# 2016_BeaconIR_YahourtPhone.net
KiCad netlist of a schematic drawn in Altium Designer
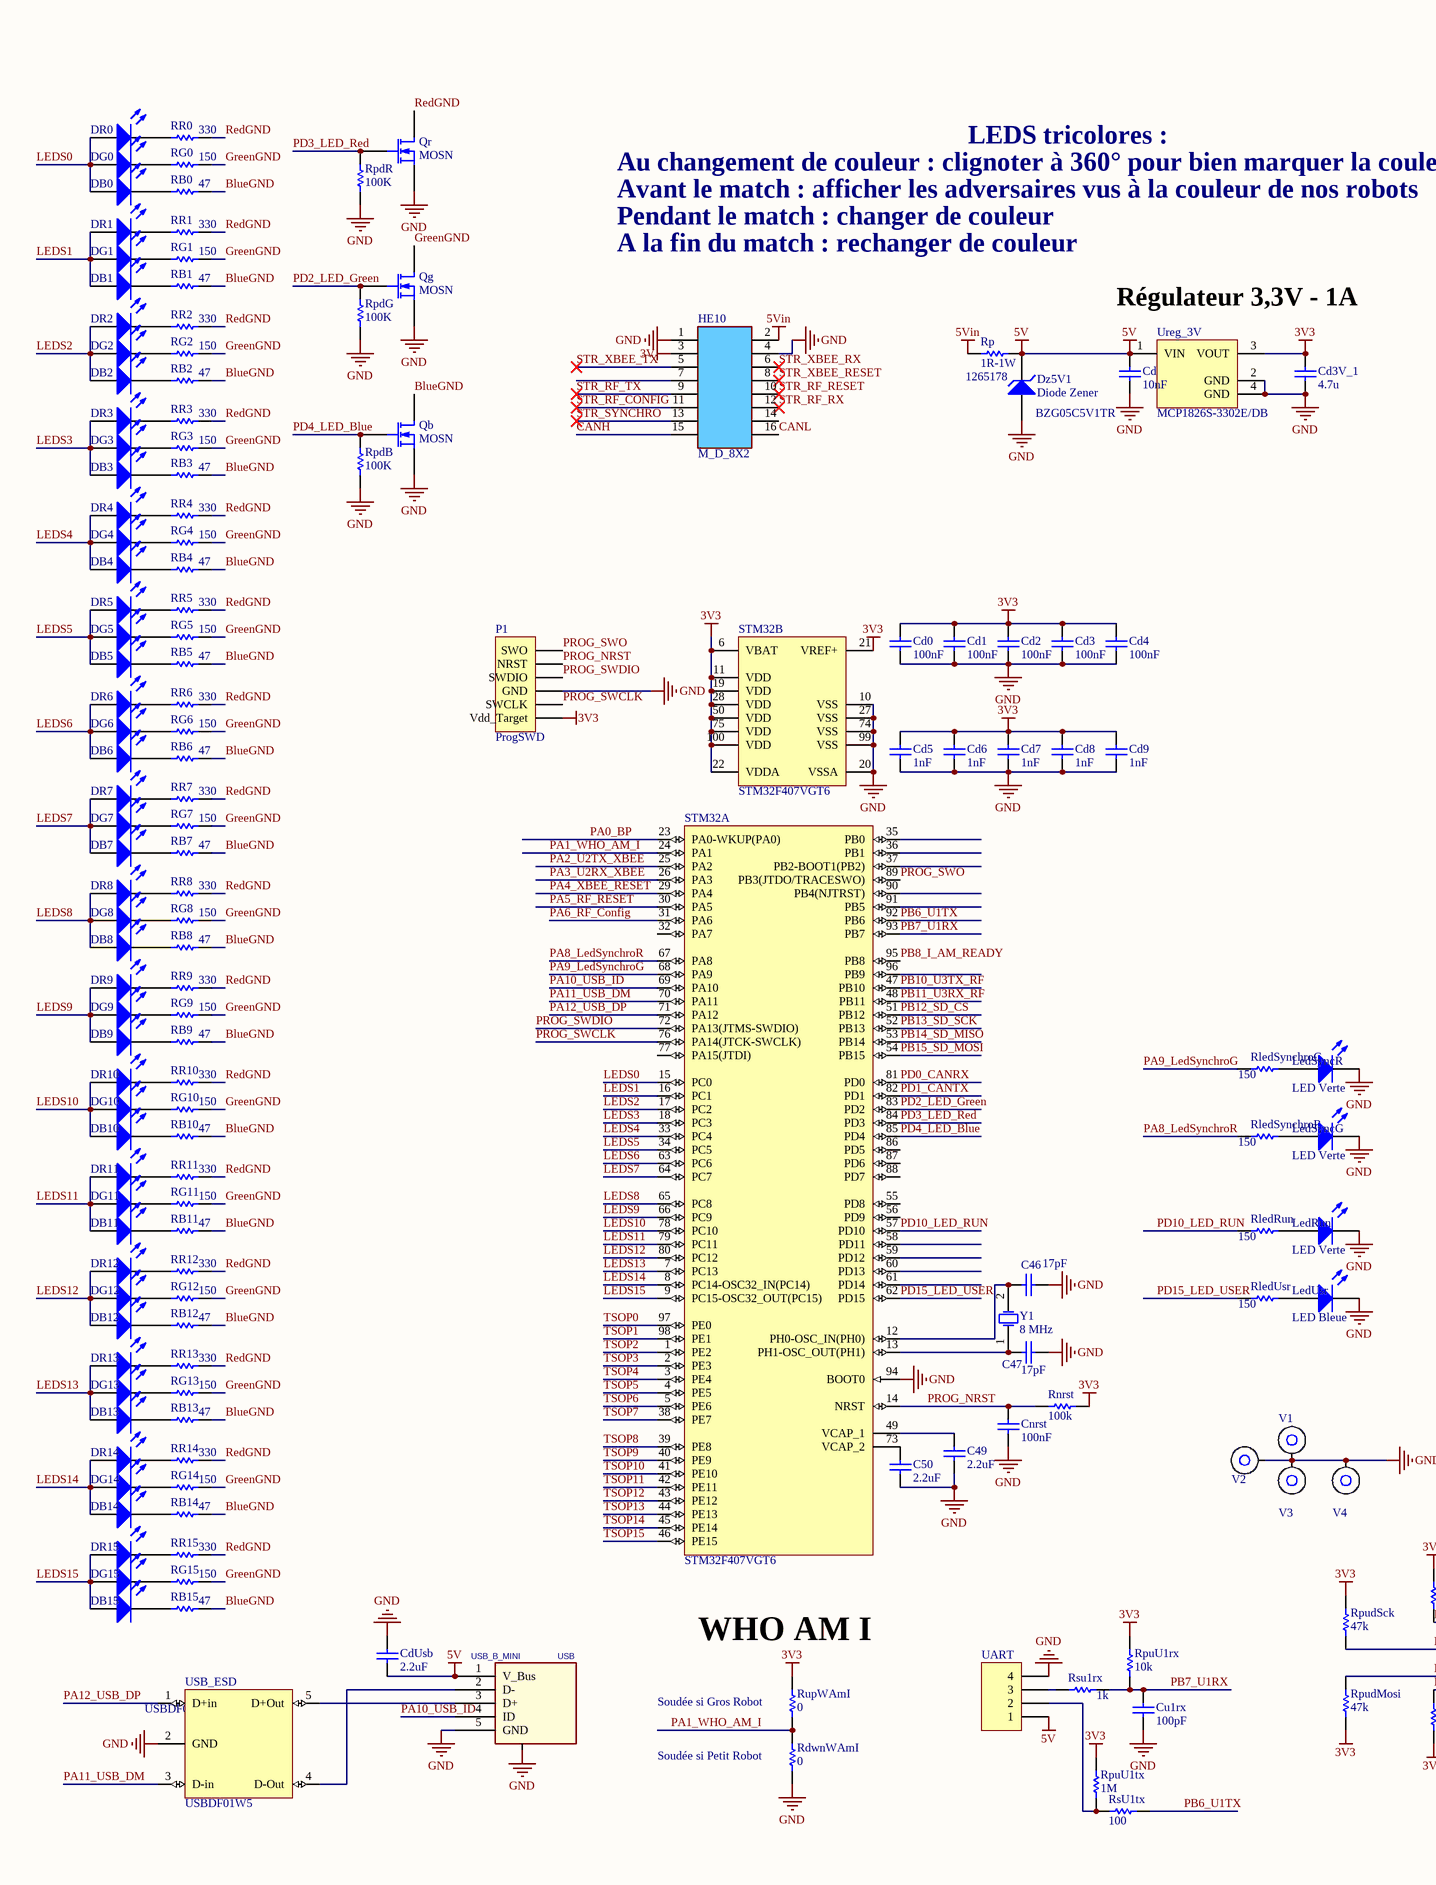
[diagram p0: 2016_BeaconIR_YahourtPhone.SchDoc, left]
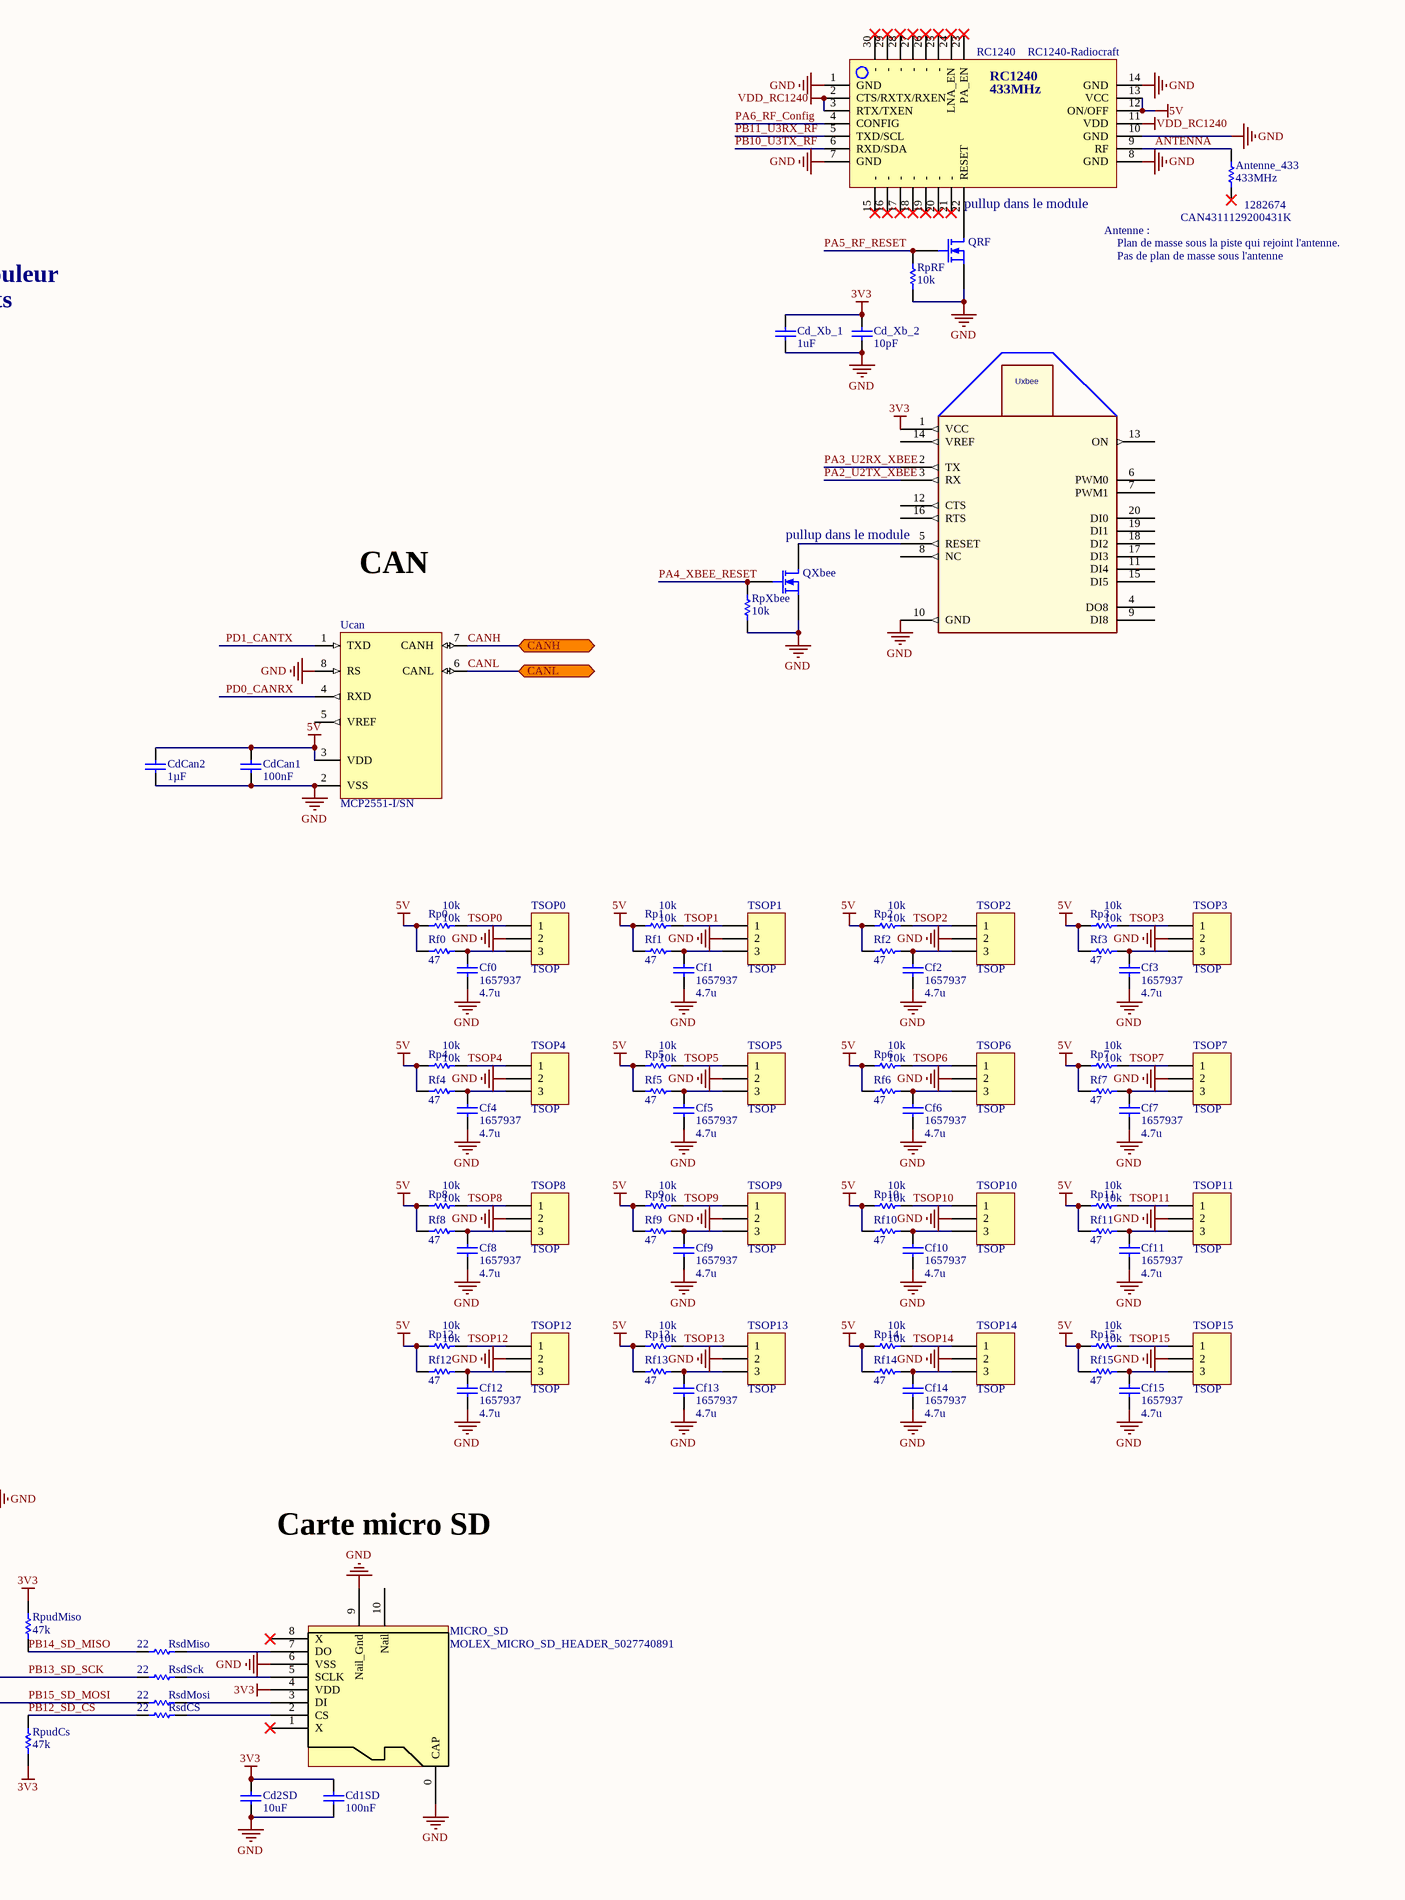
[diagram p1: 2016_BeaconIR_YahourtPhone.SchDoc, middle]
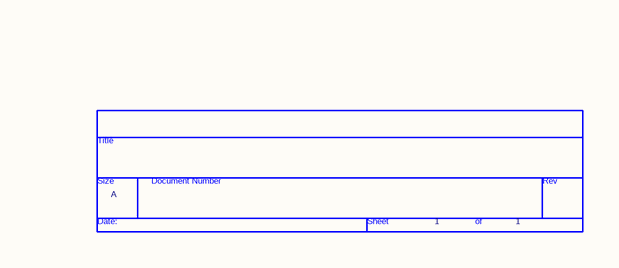
[diagram p2: 2016_BeaconIR_YahourtPhone.SchDoc, right]

(export (version "E")
  (design (tool "Eeschema 10.0.6"))
  (components
    (comp (ref "*")
      (value "TitleBlock0")
      (fields (field (name "PAGE COUNT") "1") (field (name "PAGE NUMBER") "1") (field (name "PAGE SIZE") "A"))
      (libsource (lib "*") (part "TitleBlock0"))
    )
    (comp (ref "Antenne_433")
      (value "433MHz")
      (footprint "R1206_N")
      (description "CAN4311129200431K")
      (fields
        (field (name "PACKAGEREFERENCE") "CAN4311129200431K")
        (field (name "FAR") "1282674")
        (field (name "PUBLISHER") "Altium Limited")
      )
      (libsource (lib "_ROBOT") (part "Resistor"))
    )
    (comp (ref "C46")
      (value "17pF")
      (footprint "C0805_N")
      (description "Capacitor")
      (fields (field (name "PUBLISHER") "Altium Limited"))
      (libsource (lib "_ROBOT") (part "Condensateur"))
    )
    (comp (ref "C47")
      (value "17pF")
      (footprint "C0805_N")
      (description "Capacitor")
      (fields (field (name "PUBLISHER") "Altium Limited"))
      (libsource (lib "_ROBOT") (part "Condensateur"))
    )
    (comp (ref "C49")
      (value "2.2uF")
      (footprint "C0805_N")
      (description "Capacitor")
      (fields (field (name "PUBLISHER") "Altium Limited"))
      (libsource (lib "_ROBOT") (part "Condensateur"))
    )
    (comp (ref "C50")
      (value "2.2uF")
      (footprint "C0805_N")
      (description "Capacitor")
      (fields (field (name "PUBLISHER") "Altium Limited"))
      (libsource (lib "_ROBOT") (part "Condensateur"))
    )
    (comp (ref "Cd")
      (value "10nF")
      (footprint "C1206_N")
      (description "Capacitor")
      (fields (field (name "PUBLISHER") "Altium Limited"))
      (libsource (lib "_ROBOT") (part "Condensateur"))
    )
    (comp (ref "Cd0")
      (value "100nF")
      (footprint "C0805_N")
      (description "Capacitor")
      (fields (field (name "PUBLISHER") "Altium Limited"))
      (libsource (lib "_ROBOT") (part "Condensateur"))
    )
    (comp (ref "Cd1")
      (value "100nF")
      (footprint "C0805_N")
      (description "Capacitor")
      (fields (field (name "PUBLISHER") "Altium Limited"))
      (libsource (lib "_ROBOT") (part "Condensateur"))
    )
    (comp (ref "Cd1SD")
      (value "100nF")
      (footprint "C0805_N")
      (description "Capacitor")
      (fields (field (name "PUBLISHER") "Altium Limited"))
      (libsource (lib "_ROBOT") (part "Condensateur"))
    )
    (comp (ref "Cd2")
      (value "100nF")
      (footprint "C0805_N")
      (description "Capacitor")
      (fields (field (name "PUBLISHER") "Altium Limited"))
      (libsource (lib "_ROBOT") (part "Condensateur"))
    )
    (comp (ref "Cd2SD")
      (value "10uF")
      (footprint "C1206_N")
      (description "Capacitor")
      (fields (field (name "PUBLISHER") "Altium Limited"))
      (libsource (lib "_ROBOT") (part "Condensateur"))
    )
    (comp (ref "Cd3")
      (value "100nF")
      (footprint "C0805_N")
      (description "Capacitor")
      (fields (field (name "PUBLISHER") "Altium Limited"))
      (libsource (lib "_ROBOT") (part "Condensateur"))
    )
    (comp (ref "Cd3V_1")
      (value "4.7u")
      (footprint "C0805_N")
      (description "Capacitor")
      (fields (field (name "PUBLISHER") "Altium Limited"))
      (libsource (lib "DG_Condensateur") (part "Capacitor"))
    )
    (comp (ref "Cd4")
      (value "100nF")
      (footprint "C0805_N")
      (description "Capacitor")
      (fields (field (name "PUBLISHER") "Altium Limited"))
      (libsource (lib "_ROBOT") (part "Condensateur"))
    )
    (comp (ref "Cd5")
      (value "1nF")
      (footprint "C0805_N")
      (description "Capacitor")
      (fields (field (name "PUBLISHER") "Altium Limited"))
      (libsource (lib "_ROBOT") (part "Condensateur"))
    )
    (comp (ref "Cd6")
      (value "1nF")
      (footprint "C0805_N")
      (description "Capacitor")
      (fields (field (name "PUBLISHER") "Altium Limited"))
      (libsource (lib "_ROBOT") (part "Condensateur"))
    )
    (comp (ref "Cd7")
      (value "1nF")
      (footprint "C0805_N")
      (description "Capacitor")
      (fields (field (name "PUBLISHER") "Altium Limited"))
      (libsource (lib "_ROBOT") (part "Condensateur"))
    )
    (comp (ref "Cd8")
      (value "1nF")
      (footprint "C0805_N")
      (description "Capacitor")
      (fields (field (name "PUBLISHER") "Altium Limited"))
      (libsource (lib "_ROBOT") (part "Condensateur"))
    )
    (comp (ref "Cd9")
      (value "1nF")
      (footprint "C0805_N")
      (description "Capacitor")
      (fields (field (name "PUBLISHER") "Altium Limited"))
      (libsource (lib "_ROBOT") (part "Condensateur"))
    )
    (comp (ref "CdCan1")
      (value "100nF")
      (footprint "C0805_N")
      (description "Capacitor")
      (fields (field (name "PUBLISHER") "Altium Limited"))
      (libsource (lib "_ROBOT") (part "Condensateur"))
    )
    (comp (ref "CdCan2")
      (value "1µF")
      (footprint "C0805_N")
      (description "Capacitor")
      (fields (field (name "PUBLISHER") "Altium Limited"))
      (libsource (lib "_ROBOT") (part "Condensateur"))
    )
    (comp (ref "CdUsb")
      (value "2.2uF")
      (footprint "C0805_N")
      (description "Capacitor")
      (fields (field (name "PUBLISHER") "Altium Limited"))
      (libsource (lib "_ROBOT") (part "Condensateur"))
    )
    (comp (ref "Cd_Xb_1")
      (value "1uF")
      (footprint "C0805_N")
      (description "Capacitor")
      (fields (field (name "PUBLISHER") "Altium Limited"))
      (libsource (lib "_ROBOT") (part "Condensateur"))
    )
    (comp (ref "Cd_Xb_2")
      (value "10pF")
      (footprint "C0805_N")
      (description "Capacitor")
      (fields (field (name "PUBLISHER") "Altium Limited"))
      (libsource (lib "_ROBOT") (part "Condensateur"))
    )
    (comp (ref "Cf0")
      (value "1657937")
      (footprint "C1206_N")
      (description "Capacitor")
      (fields (field (name "ALTIUM_VALUE") "4.7u") (field (name "PUBLISHER") "Altium Limited"))
      (libsource (lib "Robot2010") (part "CONDENSATEUR"))
    )
    (comp (ref "Cf1")
      (value "1657937")
      (footprint "C1206_N")
      (description "Capacitor")
      (fields (field (name "ALTIUM_VALUE") "4.7u") (field (name "PUBLISHER") "Altium Limited"))
      (libsource (lib "Robot2010") (part "CONDENSATEUR"))
    )
    (comp (ref "Cf2")
      (value "1657937")
      (footprint "C1206_N")
      (description "Capacitor")
      (fields (field (name "ALTIUM_VALUE") "4.7u") (field (name "PUBLISHER") "Altium Limited"))
      (libsource (lib "Robot2010") (part "CONDENSATEUR"))
    )
    (comp (ref "Cf3")
      (value "1657937")
      (footprint "C1206_N")
      (description "Capacitor")
      (fields (field (name "ALTIUM_VALUE") "4.7u") (field (name "PUBLISHER") "Altium Limited"))
      (libsource (lib "Robot2010") (part "CONDENSATEUR"))
    )
    (comp (ref "Cf4")
      (value "1657937")
      (footprint "C1206_N")
      (description "Capacitor")
      (fields (field (name "ALTIUM_VALUE") "4.7u") (field (name "PUBLISHER") "Altium Limited"))
      (libsource (lib "Robot2010") (part "CONDENSATEUR"))
    )
    (comp (ref "Cf5")
      (value "1657937")
      (footprint "C1206_N")
      (description "Capacitor")
      (fields (field (name "ALTIUM_VALUE") "4.7u") (field (name "PUBLISHER") "Altium Limited"))
      (libsource (lib "Robot2010") (part "CONDENSATEUR"))
    )
    (comp (ref "Cf6")
      (value "1657937")
      (footprint "C1206_N")
      (description "Capacitor")
      (fields (field (name "ALTIUM_VALUE") "4.7u") (field (name "PUBLISHER") "Altium Limited"))
      (libsource (lib "Robot2010") (part "CONDENSATEUR"))
    )
    (comp (ref "Cf7")
      (value "1657937")
      (footprint "C1206_N")
      (description "Capacitor")
      (fields (field (name "ALTIUM_VALUE") "4.7u") (field (name "PUBLISHER") "Altium Limited"))
      (libsource (lib "Robot2010") (part "CONDENSATEUR"))
    )
    (comp (ref "Cf8")
      (value "1657937")
      (footprint "C1206_N")
      (description "Capacitor")
      (fields (field (name "ALTIUM_VALUE") "4.7u") (field (name "PUBLISHER") "Altium Limited"))
      (libsource (lib "Robot2010") (part "CONDENSATEUR"))
    )
    (comp (ref "Cf9")
      (value "1657937")
      (footprint "C1206_N")
      (description "Capacitor")
      (fields (field (name "ALTIUM_VALUE") "4.7u") (field (name "PUBLISHER") "Altium Limited"))
      (libsource (lib "Robot2010") (part "CONDENSATEUR"))
    )
    (comp (ref "Cf10")
      (value "1657937")
      (footprint "C1206_N")
      (description "Capacitor")
      (fields (field (name "ALTIUM_VALUE") "4.7u") (field (name "PUBLISHER") "Altium Limited"))
      (libsource (lib "Robot2010") (part "CONDENSATEUR"))
    )
    (comp (ref "Cf11")
      (value "1657937")
      (footprint "C1206_N")
      (description "Capacitor")
      (fields (field (name "ALTIUM_VALUE") "4.7u") (field (name "PUBLISHER") "Altium Limited"))
      (libsource (lib "Robot2010") (part "CONDENSATEUR"))
    )
    (comp (ref "Cf12")
      (value "1657937")
      (footprint "C1206_N")
      (description "Capacitor")
      (fields (field (name "ALTIUM_VALUE") "4.7u") (field (name "PUBLISHER") "Altium Limited"))
      (libsource (lib "Robot2010") (part "CONDENSATEUR"))
    )
    (comp (ref "Cf13")
      (value "1657937")
      (footprint "C1206_N")
      (description "Capacitor")
      (fields (field (name "ALTIUM_VALUE") "4.7u") (field (name "PUBLISHER") "Altium Limited"))
      (libsource (lib "Robot2010") (part "CONDENSATEUR"))
    )
    (comp (ref "Cf14")
      (value "1657937")
      (footprint "C1206_N")
      (description "Capacitor")
      (fields (field (name "ALTIUM_VALUE") "4.7u") (field (name "PUBLISHER") "Altium Limited"))
      (libsource (lib "Robot2010") (part "CONDENSATEUR"))
    )
    (comp (ref "Cf15")
      (value "1657937")
      (footprint "C1206_N")
      (description "Capacitor")
      (fields (field (name "ALTIUM_VALUE") "4.7u") (field (name "PUBLISHER") "Altium Limited"))
      (libsource (lib "Robot2010") (part "CONDENSATEUR"))
    )
    (comp (ref "Cnrst")
      (value "100nF")
      (footprint "C0805_N")
      (description "Capacitor")
      (fields (field (name "PUBLISHER") "Altium Limited"))
      (libsource (lib "_ROBOT") (part "Condensateur"))
    )
    (comp (ref "Cu1rx")
      (value "100pF")
      (footprint "C0805_N")
      (description "Capacitor")
      (fields (field (name "PUBLISHER") "Altium Limited"))
      (libsource (lib "_ROBOT") (part "Condensateur"))
    )
    (comp (ref "DB0")
      (value "LED")
      (footprint "LED_sideView_1204")
      (description "Typical LED")
      (fields (field (name "PUBLISHER") "Altium Limited"))
      (libsource (lib "DG_LED") (part "LED"))
    )
    (comp (ref "DB1")
      (value "LED")
      (footprint "LED_sideView_1204")
      (description "Typical LED")
      (fields (field (name "PUBLISHER") "Altium Limited"))
      (libsource (lib "DG_LED") (part "LED"))
    )
    (comp (ref "DB2")
      (value "LED")
      (footprint "LED_sideView_1204")
      (description "Typical LED")
      (fields (field (name "PUBLISHER") "Altium Limited"))
      (libsource (lib "DG_LED") (part "LED"))
    )
    (comp (ref "DB3")
      (value "LED")
      (footprint "LED_sideView_1204")
      (description "Typical LED")
      (fields (field (name "PUBLISHER") "Altium Limited"))
      (libsource (lib "DG_LED") (part "LED"))
    )
    (comp (ref "DB4")
      (value "LED")
      (footprint "LED_sideView_1204")
      (description "Typical LED")
      (fields (field (name "PUBLISHER") "Altium Limited"))
      (libsource (lib "DG_LED") (part "LED"))
    )
    (comp (ref "DB5")
      (value "LED")
      (footprint "LED_sideView_1204")
      (description "Typical LED")
      (fields (field (name "PUBLISHER") "Altium Limited"))
      (libsource (lib "DG_LED") (part "LED"))
    )
    (comp (ref "DB6")
      (value "LED")
      (footprint "LED_sideView_1204")
      (description "Typical LED")
      (fields (field (name "PUBLISHER") "Altium Limited"))
      (libsource (lib "DG_LED") (part "LED"))
    )
    (comp (ref "DB7")
      (value "LED")
      (footprint "LED_sideView_1204")
      (description "Typical LED")
      (fields (field (name "PUBLISHER") "Altium Limited"))
      (libsource (lib "DG_LED") (part "LED"))
    )
    (comp (ref "DB8")
      (value "LED")
      (footprint "LED_sideView_1204")
      (description "Typical LED")
      (fields (field (name "PUBLISHER") "Altium Limited"))
      (libsource (lib "DG_LED") (part "LED"))
    )
    (comp (ref "DB9")
      (value "LED")
      (footprint "LED_sideView_1204")
      (description "Typical LED")
      (fields (field (name "PUBLISHER") "Altium Limited"))
      (libsource (lib "DG_LED") (part "LED"))
    )
    (comp (ref "DB10")
      (value "LED")
      (footprint "LED_sideView_1204")
      (description "Typical LED")
      (fields (field (name "PUBLISHER") "Altium Limited"))
      (libsource (lib "DG_LED") (part "LED"))
    )
    (comp (ref "DB11")
      (value "LED")
      (footprint "LED_sideView_1204")
      (description "Typical LED")
      (fields (field (name "PUBLISHER") "Altium Limited"))
      (libsource (lib "DG_LED") (part "LED"))
    )
    (comp (ref "DB12")
      (value "LED")
      (footprint "LED_sideView_1204")
      (description "Typical LED")
      (fields (field (name "PUBLISHER") "Altium Limited"))
      (libsource (lib "DG_LED") (part "LED"))
    )
    (comp (ref "DB13")
      (value "LED")
      (footprint "LED_sideView_1204")
      (description "Typical LED")
      (fields (field (name "PUBLISHER") "Altium Limited"))
      (libsource (lib "DG_LED") (part "LED"))
    )
    (comp (ref "DB14")
      (value "LED")
      (footprint "LED_sideView_1204")
      (description "Typical LED")
      (fields (field (name "PUBLISHER") "Altium Limited"))
      (libsource (lib "DG_LED") (part "LED"))
    )
    (comp (ref "DB15")
      (value "LED")
      (footprint "LED_sideView_1204")
      (description "Typical LED")
      (fields (field (name "PUBLISHER") "Altium Limited"))
      (libsource (lib "DG_LED") (part "LED"))
    )
    (comp (ref "DG0")
      (value "LED")
      (footprint "LED_sideView_1204")
      (description "Typical LED")
      (fields (field (name "PUBLISHER") "Altium Limited"))
      (libsource (lib "DG_LED") (part "LED"))
    )
    (comp (ref "DG1")
      (value "LED")
      (footprint "LED_sideView_1204")
      (description "Typical LED")
      (fields (field (name "PUBLISHER") "Altium Limited"))
      (libsource (lib "DG_LED") (part "LED"))
    )
    (comp (ref "DG2")
      (value "LED")
      (footprint "LED_sideView_1204")
      (description "Typical LED")
      (fields (field (name "PUBLISHER") "Altium Limited"))
      (libsource (lib "DG_LED") (part "LED"))
    )
    (comp (ref "DG3")
      (value "LED")
      (footprint "LED_sideView_1204")
      (description "Typical LED")
      (fields (field (name "PUBLISHER") "Altium Limited"))
      (libsource (lib "DG_LED") (part "LED"))
    )
    (comp (ref "DG4")
      (value "LED")
      (footprint "LED_sideView_1204")
      (description "Typical LED")
      (fields (field (name "PUBLISHER") "Altium Limited"))
      (libsource (lib "DG_LED") (part "LED"))
    )
    (comp (ref "DG5")
      (value "LED")
      (footprint "LED_sideView_1204")
      (description "Typical LED")
      (fields (field (name "PUBLISHER") "Altium Limited"))
      (libsource (lib "DG_LED") (part "LED"))
    )
    (comp (ref "DG6")
      (value "LED")
      (footprint "LED_sideView_1204")
      (description "Typical LED")
      (fields (field (name "PUBLISHER") "Altium Limited"))
      (libsource (lib "DG_LED") (part "LED"))
    )
    (comp (ref "DG7")
      (value "LED")
      (footprint "LED_sideView_1204")
      (description "Typical LED")
      (fields (field (name "PUBLISHER") "Altium Limited"))
      (libsource (lib "DG_LED") (part "LED"))
    )
    (comp (ref "DG8")
      (value "LED")
      (footprint "LED_sideView_1204")
      (description "Typical LED")
      (fields (field (name "PUBLISHER") "Altium Limited"))
      (libsource (lib "DG_LED") (part "LED"))
    )
    (comp (ref "DG9")
      (value "LED")
      (footprint "LED_sideView_1204")
      (description "Typical LED")
      (fields (field (name "PUBLISHER") "Altium Limited"))
      (libsource (lib "DG_LED") (part "LED"))
    )
    (comp (ref "DG10")
      (value "LED")
      (footprint "LED_sideView_1204")
      (description "Typical LED")
      (fields (field (name "PUBLISHER") "Altium Limited"))
      (libsource (lib "DG_LED") (part "LED"))
    )
    (comp (ref "DG11")
      (value "LED")
      (footprint "LED_sideView_1204")
      (description "Typical LED")
      (fields (field (name "PUBLISHER") "Altium Limited"))
      (libsource (lib "DG_LED") (part "LED"))
    )
    (comp (ref "DG12")
      (value "LED")
      (footprint "LED_sideView_1204")
      (description "Typical LED")
      (fields (field (name "PUBLISHER") "Altium Limited"))
      (libsource (lib "DG_LED") (part "LED"))
    )
    (comp (ref "DG13")
      (value "LED")
      (footprint "LED_sideView_1204")
      (description "Typical LED")
      (fields (field (name "PUBLISHER") "Altium Limited"))
      (libsource (lib "DG_LED") (part "LED"))
    )
    (comp (ref "DG14")
      (value "LED")
      (footprint "LED_sideView_1204")
      (description "Typical LED")
      (fields (field (name "PUBLISHER") "Altium Limited"))
      (libsource (lib "DG_LED") (part "LED"))
    )
    (comp (ref "DG15")
      (value "LED")
      (footprint "LED_sideView_1204")
      (description "Typical LED")
      (fields (field (name "PUBLISHER") "Altium Limited"))
      (libsource (lib "DG_LED") (part "LED"))
    )
    (comp (ref "DR0")
      (value "LED")
      (footprint "LED_sideView_1204")
      (description "Typical LED")
      (fields (field (name "PUBLISHER") "Altium Limited"))
      (libsource (lib "DG_LED") (part "LED"))
    )
    (comp (ref "DR1")
      (value "LED")
      (footprint "LED_sideView_1204")
      (description "Typical LED")
      (fields (field (name "PUBLISHER") "Altium Limited"))
      (libsource (lib "DG_LED") (part "LED"))
    )
    (comp (ref "DR2")
      (value "LED")
      (footprint "LED_sideView_1204")
      (description "Typical LED")
      (fields (field (name "PUBLISHER") "Altium Limited"))
      (libsource (lib "DG_LED") (part "LED"))
    )
    (comp (ref "DR3")
      (value "LED")
      (footprint "LED_sideView_1204")
      (description "Typical LED")
      (fields (field (name "PUBLISHER") "Altium Limited"))
      (libsource (lib "DG_LED") (part "LED"))
    )
    (comp (ref "DR4")
      (value "LED")
      (footprint "LED_sideView_1204")
      (description "Typical LED")
      (fields (field (name "PUBLISHER") "Altium Limited"))
      (libsource (lib "DG_LED") (part "LED"))
    )
    (comp (ref "DR5")
      (value "LED")
      (footprint "LED_sideView_1204")
      (description "Typical LED")
      (fields (field (name "PUBLISHER") "Altium Limited"))
      (libsource (lib "DG_LED") (part "LED"))
    )
    (comp (ref "DR6")
      (value "LED")
      (footprint "LED_sideView_1204")
      (description "Typical LED")
      (fields (field (name "PUBLISHER") "Altium Limited"))
      (libsource (lib "DG_LED") (part "LED"))
    )
    (comp (ref "DR7")
      (value "LED")
      (footprint "LED_sideView_1204")
      (description "Typical LED")
      (fields (field (name "PUBLISHER") "Altium Limited"))
      (libsource (lib "DG_LED") (part "LED"))
    )
    (comp (ref "DR8")
      (value "LED")
      (footprint "LED_sideView_1204")
      (description "Typical LED")
      (fields (field (name "PUBLISHER") "Altium Limited"))
      (libsource (lib "DG_LED") (part "LED"))
    )
    (comp (ref "DR9")
      (value "LED")
      (footprint "LED_sideView_1204")
      (description "Typical LED")
      (fields (field (name "PUBLISHER") "Altium Limited"))
      (libsource (lib "DG_LED") (part "LED"))
    )
    (comp (ref "DR10")
      (value "LED")
      (footprint "LED_sideView_1204")
      (description "Typical LED")
      (fields (field (name "PUBLISHER") "Altium Limited"))
      (libsource (lib "DG_LED") (part "LED"))
    )
    (comp (ref "DR11")
      (value "LED")
      (footprint "LED_sideView_1204")
      (description "Typical LED")
      (fields (field (name "PUBLISHER") "Altium Limited"))
      (libsource (lib "DG_LED") (part "LED"))
    )
    (comp (ref "DR12")
      (value "LED")
      (footprint "LED_sideView_1204")
      (description "Typical LED")
      (fields (field (name "PUBLISHER") "Altium Limited"))
      (libsource (lib "DG_LED") (part "LED"))
    )
    (comp (ref "DR13")
      (value "LED")
      (footprint "LED_sideView_1204")
      (description "Typical LED")
      (fields (field (name "PUBLISHER") "Altium Limited"))
      (libsource (lib "DG_LED") (part "LED"))
    )
    (comp (ref "DR14")
      (value "LED")
      (footprint "LED_sideView_1204")
      (description "Typical LED")
      (fields (field (name "PUBLISHER") "Altium Limited"))
      (libsource (lib "DG_LED") (part "LED"))
    )
    (comp (ref "DR15")
      (value "LED")
      (footprint "LED_sideView_1204")
      (description "Typical LED")
      (fields (field (name "PUBLISHER") "Altium Limited"))
      (libsource (lib "DG_LED") (part "LED"))
    )
    (comp (ref "Dz5V1")
      (value "Diode Zener")
      (footprint "SMA Diode")
      (description "Zener Diode")
      (fields (field (name "ALTIUM_UNNAMED_1") "BZG05C5V1TR"))
      (libsource (lib "_ROBOT") (part "Diode Zener"))
    )
    (comp (ref "HE10")
      (value "BARRETTE_8 CONTACTS_2 RANGEES_MALE_DROITE")
      (footprint "HE10/16_M_D_B P")
      (fields (field (name "TYPE") "M_D_8X2"))
      (libsource (lib "connecteurs") (part "BARRETTE_8 CONTACTS_2 RANGEES_MALE_DROITE"))
    )
    (comp (ref "LedRun")
      (value "LED Verte")
      (footprint "LED_0805")
      (description "Typical LED")
      (fields (field (name "PUBLISHER") "Altium Limited"))
      (libsource (lib "DG_LED") (part "LED"))
    )
    (comp (ref "LedSyncG")
      (value "LED Verte")
      (footprint "LED_0805")
      (description "Typical LED")
      (fields (field (name "PUBLISHER") "Altium Limited"))
      (libsource (lib "DG_LED") (part "LED"))
    )
    (comp (ref "LedSyncR")
      (value "LED Verte")
      (footprint "LED_0805")
      (description "Typical LED")
      (fields (field (name "PUBLISHER") "Altium Limited"))
      (libsource (lib "DG_LED") (part "LED"))
    )
    (comp (ref "LedUsr")
      (value "LED Bleue")
      (footprint "LED_0805")
      (description "Typical LED")
      (fields (field (name "PUBLISHER") "Altium Limited"))
      (libsource (lib "DG_LED") (part "LED"))
    )
    (comp (ref "MICRO_SD")
      (value "MOLEX_MICRO_SD_HEADER_5027740891")
      (footprint "MOLEX_MICRO_SD_HEADER_5027740891")
      (libsource (lib "Connecteur") (part "MOLEX_MICRO_SD_HEADER_5027740891"))
    )
    (comp (ref "P1")
      (value "ProgSWD")
      (footprint "HDR1X6")
      (description "Header, 6-Pin")
      (fields (field (name "PUBLISHER") "Altium Limited"))
      (libsource (lib "DG_Connecteur") (part "Header 6"))
    )
    (comp (ref "Qb")
      (value "MOSN")
      (footprint "SOT23-3N")
      (description "N-Channel MOSFET")
      (fields (field (name "PUBLISHER") "Altium Limited"))
      (libsource (lib "_ROBOT") (part "Transistor MOSFET-N"))
    )
    (comp (ref "Qg")
      (value "MOSN")
      (footprint "SOT23-3N")
      (description "N-Channel MOSFET")
      (fields (field (name "PUBLISHER") "Altium Limited"))
      (libsource (lib "_ROBOT") (part "Transistor MOSFET-N"))
    )
    (comp (ref "Qr")
      (value "MOSN")
      (footprint "SOT23-3N")
      (description "N-Channel MOSFET")
      (fields (field (name "PUBLISHER") "Altium Limited"))
      (libsource (lib "_ROBOT") (part "Transistor MOSFET-N"))
    )
    (comp (ref "QRF")
      (value "Transistor MOSFET-N")
      (footprint "SOT23-3N")
      (description "N-Channel MOSFET")
      (fields (field (name "PUBLISHER") "Altium Limited"))
      (libsource (lib "_ROBOT") (part "Transistor MOSFET-N"))
    )
    (comp (ref "QXbee")
      (value "Transistor MOSFET-N")
      (footprint "SOT23-3N")
      (description "N-Channel MOSFET")
      (fields (field (name "PUBLISHER") "Altium Limited"))
      (libsource (lib "_ROBOT") (part "Transistor MOSFET-N"))
    )
    (comp (ref "RB0")
      (value "47")
      (footprint "R1206_N")
      (description "Resistor")
      (fields (field (name "PUBLISHER") "Altium Limited"))
      (libsource (lib "_ROBOT") (part "Resistor"))
    )
    (comp (ref "RB1")
      (value "47")
      (footprint "R1206_N")
      (description "Resistor")
      (fields (field (name "PUBLISHER") "Altium Limited"))
      (libsource (lib "_ROBOT") (part "Resistor"))
    )
    (comp (ref "RB2")
      (value "47")
      (footprint "R1206_N")
      (description "Resistor")
      (fields (field (name "PUBLISHER") "Altium Limited"))
      (libsource (lib "_ROBOT") (part "Resistor"))
    )
    (comp (ref "RB3")
      (value "47")
      (footprint "R1206_N")
      (description "Resistor")
      (fields (field (name "PUBLISHER") "Altium Limited"))
      (libsource (lib "_ROBOT") (part "Resistor"))
    )
    (comp (ref "RB4")
      (value "47")
      (footprint "R1206_N")
      (description "Resistor")
      (fields (field (name "PUBLISHER") "Altium Limited"))
      (libsource (lib "_ROBOT") (part "Resistor"))
    )
    (comp (ref "RB5")
      (value "47")
      (footprint "R1206_N")
      (description "Resistor")
      (fields (field (name "PUBLISHER") "Altium Limited"))
      (libsource (lib "_ROBOT") (part "Resistor"))
    )
    (comp (ref "RB6")
      (value "47")
      (footprint "R1206_N")
      (description "Resistor")
      (fields (field (name "PUBLISHER") "Altium Limited"))
      (libsource (lib "_ROBOT") (part "Resistor"))
    )
    (comp (ref "RB7")
      (value "47")
      (footprint "R1206_N")
      (description "Resistor")
      (fields (field (name "PUBLISHER") "Altium Limited"))
      (libsource (lib "_ROBOT") (part "Resistor"))
    )
    (comp (ref "RB8")
      (value "47")
      (footprint "R1206_N")
      (description "Resistor")
      (fields (field (name "PUBLISHER") "Altium Limited"))
      (libsource (lib "_ROBOT") (part "Resistor"))
    )
    (comp (ref "RB9")
      (value "47")
      (footprint "R1206_N")
      (description "Resistor")
      (fields (field (name "PUBLISHER") "Altium Limited"))
      (libsource (lib "_ROBOT") (part "Resistor"))
    )
    (comp (ref "RB10")
      (value "47")
      (footprint "R1206_N")
      (description "Resistor")
      (fields (field (name "PUBLISHER") "Altium Limited"))
      (libsource (lib "_ROBOT") (part "Resistor"))
    )
    (comp (ref "RB11")
      (value "47")
      (footprint "R1206_N")
      (description "Resistor")
      (fields (field (name "PUBLISHER") "Altium Limited"))
      (libsource (lib "_ROBOT") (part "Resistor"))
    )
    (comp (ref "RB12")
      (value "47")
      (footprint "R1206_N")
      (description "Resistor")
      (fields (field (name "PUBLISHER") "Altium Limited"))
      (libsource (lib "_ROBOT") (part "Resistor"))
    )
    (comp (ref "RB13")
      (value "47")
      (footprint "R1206_N")
      (description "Resistor")
      (fields (field (name "PUBLISHER") "Altium Limited"))
      (libsource (lib "_ROBOT") (part "Resistor"))
    )
    (comp (ref "RB14")
      (value "47")
      (footprint "R1206_N")
      (description "Resistor")
      (fields (field (name "PUBLISHER") "Altium Limited"))
      (libsource (lib "_ROBOT") (part "Resistor"))
    )
    (comp (ref "RB15")
      (value "47")
      (footprint "R1206_N")
      (description "Resistor")
      (fields (field (name "PUBLISHER") "Altium Limited"))
      (libsource (lib "_ROBOT") (part "Resistor"))
    )
    (comp (ref "RC1240")
      (value "RC1240-Radiocraft")
      (footprint "RC1240")
      (description "RC1240 - Radiocraft 433MHz Transceiver")
      (libsource (lib "_ROBOT") (part "RC1240-Radiocraft"))
    )
    (comp (ref "RdwnWAmI")
      (value "0")
      (footprint "R1206_N")
      (description "Resistor")
      (fields (field (name "PUBLISHER") "Altium Limited"))
      (libsource (lib "_ROBOT") (part "Resistor"))
    )
    (comp (ref "Rf0")
      (value "47")
      (footprint "R1206_N")
      (description "Resistor")
      (fields (field (name "PUBLISHER") "Altium Limited"))
      (libsource (lib "Robot2010") (part "RESISTANCE"))
    )
    (comp (ref "Rf1")
      (value "47")
      (footprint "R1206_N")
      (description "Resistor")
      (fields (field (name "PUBLISHER") "Altium Limited"))
      (libsource (lib "Robot2010") (part "RESISTANCE"))
    )
    (comp (ref "Rf2")
      (value "47")
      (footprint "R1206_N")
      (description "Resistor")
      (fields (field (name "PUBLISHER") "Altium Limited"))
      (libsource (lib "Robot2010") (part "RESISTANCE"))
    )
    (comp (ref "Rf3")
      (value "47")
      (footprint "R1206_N")
      (description "Resistor")
      (fields (field (name "PUBLISHER") "Altium Limited"))
      (libsource (lib "Robot2010") (part "RESISTANCE"))
    )
    (comp (ref "Rf4")
      (value "47")
      (footprint "R1206_N")
      (description "Resistor")
      (fields (field (name "PUBLISHER") "Altium Limited"))
      (libsource (lib "Robot2010") (part "RESISTANCE"))
    )
    (comp (ref "Rf5")
      (value "47")
      (footprint "R1206_N")
      (description "Resistor")
      (fields (field (name "PUBLISHER") "Altium Limited"))
      (libsource (lib "Robot2010") (part "RESISTANCE"))
    )
    (comp (ref "Rf6")
      (value "47")
      (footprint "R1206_N")
      (description "Resistor")
      (fields (field (name "PUBLISHER") "Altium Limited"))
      (libsource (lib "Robot2010") (part "RESISTANCE"))
    )
    (comp (ref "Rf7")
      (value "47")
      (footprint "R1206_N")
      (description "Resistor")
      (fields (field (name "PUBLISHER") "Altium Limited"))
      (libsource (lib "Robot2010") (part "RESISTANCE"))
    )
    (comp (ref "Rf8")
      (value "47")
      (footprint "R1206_N")
      (description "Resistor")
      (fields (field (name "PUBLISHER") "Altium Limited"))
      (libsource (lib "Robot2010") (part "RESISTANCE"))
    )
    (comp (ref "Rf9")
      (value "47")
      (footprint "R1206_N")
      (description "Resistor")
      (fields (field (name "PUBLISHER") "Altium Limited"))
      (libsource (lib "Robot2010") (part "RESISTANCE"))
    )
    (comp (ref "Rf10")
      (value "47")
      (footprint "R1206_N")
      (description "Resistor")
      (fields (field (name "PUBLISHER") "Altium Limited"))
      (libsource (lib "Robot2010") (part "RESISTANCE"))
    )
    (comp (ref "Rf11")
      (value "47")
      (footprint "R1206_N")
      (description "Resistor")
      (fields (field (name "PUBLISHER") "Altium Limited"))
      (libsource (lib "Robot2010") (part "RESISTANCE"))
    )
    (comp (ref "Rf12")
      (value "47")
      (footprint "R1206_N")
      (description "Resistor")
      (fields (field (name "PUBLISHER") "Altium Limited"))
      (libsource (lib "Robot2010") (part "RESISTANCE"))
    )
    (comp (ref "Rf13")
      (value "47")
      (footprint "R1206_N")
      (description "Resistor")
      (fields (field (name "PUBLISHER") "Altium Limited"))
      (libsource (lib "Robot2010") (part "RESISTANCE"))
    )
    (comp (ref "Rf14")
      (value "47")
      (footprint "R1206_N")
      (description "Resistor")
      (fields (field (name "PUBLISHER") "Altium Limited"))
      (libsource (lib "Robot2010") (part "RESISTANCE"))
    )
    (comp (ref "Rf15")
      (value "47")
      (footprint "R1206_N")
      (description "Resistor")
      (fields (field (name "PUBLISHER") "Altium Limited"))
      (libsource (lib "Robot2010") (part "RESISTANCE"))
    )
    (comp (ref "RG0")
      (value "150")
      (footprint "R1206_N")
      (description "Resistor")
      (fields (field (name "PUBLISHER") "Altium Limited"))
      (libsource (lib "_ROBOT") (part "Resistor"))
    )
    (comp (ref "RG1")
      (value "150")
      (footprint "R1206_N")
      (description "Resistor")
      (fields (field (name "PUBLISHER") "Altium Limited"))
      (libsource (lib "_ROBOT") (part "Resistor"))
    )
    (comp (ref "RG2")
      (value "150")
      (footprint "R1206_N")
      (description "Resistor")
      (fields (field (name "PUBLISHER") "Altium Limited"))
      (libsource (lib "_ROBOT") (part "Resistor"))
    )
    (comp (ref "RG3")
      (value "150")
      (footprint "R1206_N")
      (description "Resistor")
      (fields (field (name "PUBLISHER") "Altium Limited"))
      (libsource (lib "_ROBOT") (part "Resistor"))
    )
    (comp (ref "RG4")
      (value "150")
      (footprint "R1206_N")
      (description "Resistor")
      (fields (field (name "PUBLISHER") "Altium Limited"))
      (libsource (lib "_ROBOT") (part "Resistor"))
    )
    (comp (ref "RG5")
      (value "150")
      (footprint "R1206_N")
      (description "Resistor")
      (fields (field (name "PUBLISHER") "Altium Limited"))
      (libsource (lib "_ROBOT") (part "Resistor"))
    )
    (comp (ref "RG6")
      (value "150")
      (footprint "R1206_N")
      (description "Resistor")
      (fields (field (name "PUBLISHER") "Altium Limited"))
      (libsource (lib "_ROBOT") (part "Resistor"))
    )
    (comp (ref "RG7")
      (value "150")
      (footprint "R1206_N")
      (description "Resistor")
      (fields (field (name "PUBLISHER") "Altium Limited"))
      (libsource (lib "_ROBOT") (part "Resistor"))
    )
    (comp (ref "RG8")
      (value "150")
      (footprint "R1206_N")
      (description "Resistor")
      (fields (field (name "PUBLISHER") "Altium Limited"))
      (libsource (lib "_ROBOT") (part "Resistor"))
    )
    (comp (ref "RG9")
      (value "150")
      (footprint "R1206_N")
      (description "Resistor")
      (fields (field (name "PUBLISHER") "Altium Limited"))
      (libsource (lib "_ROBOT") (part "Resistor"))
    )
    (comp (ref "RG10")
      (value "150")
      (footprint "R1206_N")
      (description "Resistor")
      (fields (field (name "PUBLISHER") "Altium Limited"))
      (libsource (lib "_ROBOT") (part "Resistor"))
    )
    (comp (ref "RG11")
      (value "150")
      (footprint "R1206_N")
      (description "Resistor")
      (fields (field (name "PUBLISHER") "Altium Limited"))
      (libsource (lib "_ROBOT") (part "Resistor"))
    )
    (comp (ref "RG12")
      (value "150")
      (footprint "R1206_N")
      (description "Resistor")
      (fields (field (name "PUBLISHER") "Altium Limited"))
      (libsource (lib "_ROBOT") (part "Resistor"))
    )
    (comp (ref "RG13")
      (value "150")
      (footprint "R1206_N")
      (description "Resistor")
      (fields (field (name "PUBLISHER") "Altium Limited"))
      (libsource (lib "_ROBOT") (part "Resistor"))
    )
    (comp (ref "RG14")
      (value "150")
      (footprint "R1206_N")
      (description "Resistor")
      (fields (field (name "PUBLISHER") "Altium Limited"))
      (libsource (lib "_ROBOT") (part "Resistor"))
    )
    (comp (ref "RG15")
      (value "150")
      (footprint "R1206_N")
      (description "Resistor")
      (fields (field (name "PUBLISHER") "Altium Limited"))
      (libsource (lib "_ROBOT") (part "Resistor"))
    )
    (comp (ref "RledRun")
      (value "150")
      (footprint "R1206_N")
      (description "Resistor")
      (fields (field (name "PUBLISHER") "Altium Limited"))
      (libsource (lib "_ROBOT") (part "Resistor"))
    )
    (comp (ref "RledSynchroG")
      (value "150")
      (footprint "R1206_N")
      (description "Resistor")
      (fields (field (name "PUBLISHER") "Altium Limited"))
      (libsource (lib "_ROBOT") (part "Resistor"))
    )
    (comp (ref "RledSynchroR")
      (value "150")
      (footprint "R1206_N")
      (description "Resistor")
      (fields (field (name "PUBLISHER") "Altium Limited"))
      (libsource (lib "_ROBOT") (part "Resistor"))
    )
    (comp (ref "RledUsr")
      (value "150")
      (footprint "R1206_N")
      (description "Resistor")
      (fields (field (name "PUBLISHER") "Altium Limited"))
      (libsource (lib "_ROBOT") (part "Resistor"))
    )
    (comp (ref "Rnrst")
      (value "100k")
      (footprint "R1206_N")
      (description "Resistor")
      (fields (field (name "PUBLISHER") "Altium Limited"))
      (libsource (lib "_ROBOT") (part "Resistor"))
    )
    (comp (ref "Rp")
      (value "1R-1W")
      (footprint "INDUCTANCE_CMS_1812")
      (description "Resistor")
      (fields (field (name "FAR") "1265178") (field (name "PUBLISHER") "Altium Limited"))
      (libsource (lib "_ROBOT") (part "Resistor"))
    )
    (comp (ref "Rp0")
      (value "10k")
      (footprint "R1206_N")
      (description "Resistor")
      (fields (field (name "ALTIUM_VALUE") "10k") (field (name "PUBLISHER") "Altium Limited"))
      (libsource (lib "Robot2010") (part "RESISTANCE"))
    )
    (comp (ref "Rp1")
      (value "10k")
      (footprint "R1206_N")
      (description "Resistor")
      (fields (field (name "ALTIUM_VALUE") "10k") (field (name "PUBLISHER") "Altium Limited"))
      (libsource (lib "Robot2010") (part "RESISTANCE"))
    )
    (comp (ref "Rp2")
      (value "10k")
      (footprint "R1206_N")
      (description "Resistor")
      (fields (field (name "ALTIUM_VALUE") "10k") (field (name "PUBLISHER") "Altium Limited"))
      (libsource (lib "Robot2010") (part "RESISTANCE"))
    )
    (comp (ref "Rp3")
      (value "10k")
      (footprint "R1206_N")
      (description "Resistor")
      (fields (field (name "ALTIUM_VALUE") "10k") (field (name "PUBLISHER") "Altium Limited"))
      (libsource (lib "Robot2010") (part "RESISTANCE"))
    )
    (comp (ref "Rp4")
      (value "10k")
      (footprint "R1206_N")
      (description "Resistor")
      (fields (field (name "ALTIUM_VALUE") "10k") (field (name "PUBLISHER") "Altium Limited"))
      (libsource (lib "Robot2010") (part "RESISTANCE"))
    )
    (comp (ref "Rp5")
      (value "10k")
      (footprint "R1206_N")
      (description "Resistor")
      (fields (field (name "ALTIUM_VALUE") "10k") (field (name "PUBLISHER") "Altium Limited"))
      (libsource (lib "Robot2010") (part "RESISTANCE"))
    )
    (comp (ref "Rp6")
      (value "10k")
      (footprint "R1206_N")
      (description "Resistor")
      (fields (field (name "ALTIUM_VALUE") "10k") (field (name "PUBLISHER") "Altium Limited"))
      (libsource (lib "Robot2010") (part "RESISTANCE"))
    )
    (comp (ref "Rp7")
      (value "10k")
      (footprint "R1206_N")
      (description "Resistor")
      (fields (field (name "ALTIUM_VALUE") "10k") (field (name "PUBLISHER") "Altium Limited"))
      (libsource (lib "Robot2010") (part "RESISTANCE"))
    )
    (comp (ref "Rp8")
      (value "10k")
      (footprint "R1206_N")
      (description "Resistor")
      (fields (field (name "ALTIUM_VALUE") "10k") (field (name "PUBLISHER") "Altium Limited"))
      (libsource (lib "Robot2010") (part "RESISTANCE"))
    )
    (comp (ref "Rp9")
      (value "10k")
      (footprint "R1206_N")
      (description "Resistor")
      (fields (field (name "ALTIUM_VALUE") "10k") (field (name "PUBLISHER") "Altium Limited"))
      (libsource (lib "Robot2010") (part "RESISTANCE"))
    )
    (comp (ref "Rp10")
      (value "10k")
      (footprint "R1206_N")
      (description "Resistor")
      (fields (field (name "ALTIUM_VALUE") "10k") (field (name "PUBLISHER") "Altium Limited"))
      (libsource (lib "Robot2010") (part "RESISTANCE"))
    )
    (comp (ref "Rp11")
      (value "10k")
      (footprint "R1206_N")
      (description "Resistor")
      (fields (field (name "ALTIUM_VALUE") "10k") (field (name "PUBLISHER") "Altium Limited"))
      (libsource (lib "Robot2010") (part "RESISTANCE"))
    )
    (comp (ref "Rp12")
      (value "10k")
      (footprint "R1206_N")
      (description "Resistor")
      (fields (field (name "ALTIUM_VALUE") "10k") (field (name "PUBLISHER") "Altium Limited"))
      (libsource (lib "Robot2010") (part "RESISTANCE"))
    )
    (comp (ref "Rp13")
      (value "10k")
      (footprint "R1206_N")
      (description "Resistor")
      (fields (field (name "ALTIUM_VALUE") "10k") (field (name "PUBLISHER") "Altium Limited"))
      (libsource (lib "Robot2010") (part "RESISTANCE"))
    )
    (comp (ref "Rp14")
      (value "10k")
      (footprint "R1206_N")
      (description "Resistor")
      (fields (field (name "ALTIUM_VALUE") "10k") (field (name "PUBLISHER") "Altium Limited"))
      (libsource (lib "Robot2010") (part "RESISTANCE"))
    )
    (comp (ref "Rp15")
      (value "10k")
      (footprint "R1206_N")
      (description "Resistor")
      (fields (field (name "ALTIUM_VALUE") "10k") (field (name "PUBLISHER") "Altium Limited"))
      (libsource (lib "Robot2010") (part "RESISTANCE"))
    )
    (comp (ref "RpdB")
      (value "100K")
      (footprint "R1206_N")
      (description "Resistor")
      (fields (field (name "PUBLISHER") "Altium Limited"))
      (libsource (lib "_ROBOT") (part "Resistor"))
    )
    (comp (ref "RpdG")
      (value "100K")
      (footprint "R1206_N")
      (description "Resistor")
      (fields (field (name "PUBLISHER") "Altium Limited"))
      (libsource (lib "_ROBOT") (part "Resistor"))
    )
    (comp (ref "RpdR")
      (value "100K")
      (footprint "R1206_N")
      (description "Resistor")
      (fields (field (name "PUBLISHER") "Altium Limited"))
      (libsource (lib "_ROBOT") (part "Resistor"))
    )
    (comp (ref "RpRF")
      (value "10k")
      (footprint "R1206_N")
      (description "Resistor")
      (fields (field (name "PUBLISHER") "Altium Limited"))
      (libsource (lib "_ROBOT") (part "Resistor"))
    )
    (comp (ref "RpudCs")
      (value "47k")
      (footprint "R1206_N")
      (description "Resistor")
      (fields (field (name "PUBLISHER") "Altium Limited"))
      (libsource (lib "_ROBOT") (part "Resistor"))
    )
    (comp (ref "RpudMiso")
      (value "47k")
      (footprint "R1206_N")
      (description "Resistor")
      (fields (field (name "PUBLISHER") "Altium Limited"))
      (libsource (lib "_ROBOT") (part "Resistor"))
    )
    (comp (ref "RpudMosi")
      (value "47k")
      (footprint "R1206_N")
      (description "Resistor")
      (fields (field (name "PUBLISHER") "Altium Limited"))
      (libsource (lib "_ROBOT") (part "Resistor"))
    )
    (comp (ref "RpudSck")
      (value "47k")
      (footprint "R1206_N")
      (description "Resistor")
      (fields (field (name "PUBLISHER") "Altium Limited"))
      (libsource (lib "_ROBOT") (part "Resistor"))
    )
    (comp (ref "RpuU1rx")
      (value "10k")
      (footprint "R1206_N")
      (description "Resistor")
      (fields (field (name "PUBLISHER") "Altium Limited"))
      (libsource (lib "_ROBOT") (part "Resistor"))
    )
    (comp (ref "RpuU1tx")
      (value "1M")
      (footprint "R1206_N")
      (description "Resistor")
      (fields (field (name "PUBLISHER") "Altium Limited"))
      (libsource (lib "_ROBOT") (part "Resistor"))
    )
    (comp (ref "RpXbee")
      (value "10k")
      (footprint "R1206_N")
      (description "Resistor")
      (fields (field (name "PUBLISHER") "Altium Limited"))
      (libsource (lib "_ROBOT") (part "Resistor"))
    )
    (comp (ref "RR0")
      (value "330")
      (footprint "R1206_N")
      (description "Resistor")
      (fields (field (name "PUBLISHER") "Altium Limited"))
      (libsource (lib "_ROBOT") (part "Resistor"))
    )
    (comp (ref "RR1")
      (value "330")
      (footprint "R1206_N")
      (description "Resistor")
      (fields (field (name "PUBLISHER") "Altium Limited"))
      (libsource (lib "_ROBOT") (part "Resistor"))
    )
    (comp (ref "RR2")
      (value "330")
      (footprint "R1206_N")
      (description "Resistor")
      (fields (field (name "PUBLISHER") "Altium Limited"))
      (libsource (lib "_ROBOT") (part "Resistor"))
    )
    (comp (ref "RR3")
      (value "330")
      (footprint "R1206_N")
      (description "Resistor")
      (fields (field (name "PUBLISHER") "Altium Limited"))
      (libsource (lib "_ROBOT") (part "Resistor"))
    )
    (comp (ref "RR4")
      (value "330")
      (footprint "R1206_N")
      (description "Resistor")
      (fields (field (name "PUBLISHER") "Altium Limited"))
      (libsource (lib "_ROBOT") (part "Resistor"))
    )
    (comp (ref "RR5")
      (value "330")
      (footprint "R1206_N")
      (description "Resistor")
      (fields (field (name "PUBLISHER") "Altium Limited"))
      (libsource (lib "_ROBOT") (part "Resistor"))
    )
    (comp (ref "RR6")
      (value "330")
      (footprint "R1206_N")
      (description "Resistor")
      (fields (field (name "PUBLISHER") "Altium Limited"))
      (libsource (lib "_ROBOT") (part "Resistor"))
    )
    (comp (ref "RR7")
      (value "330")
      (footprint "R1206_N")
      (description "Resistor")
      (fields (field (name "PUBLISHER") "Altium Limited"))
      (libsource (lib "_ROBOT") (part "Resistor"))
    )
    (comp (ref "RR8")
      (value "330")
      (footprint "R1206_N")
      (description "Resistor")
      (fields (field (name "PUBLISHER") "Altium Limited"))
      (libsource (lib "_ROBOT") (part "Resistor"))
    )
    (comp (ref "RR9")
      (value "330")
      (footprint "R1206_N")
      (description "Resistor")
      (fields (field (name "PUBLISHER") "Altium Limited"))
      (libsource (lib "_ROBOT") (part "Resistor"))
    )
    (comp (ref "RR10")
      (value "330")
      (footprint "R1206_N")
      (description "Resistor")
      (fields (field (name "PUBLISHER") "Altium Limited"))
      (libsource (lib "_ROBOT") (part "Resistor"))
    )
    (comp (ref "RR11")
      (value "330")
      (footprint "R1206_N")
      (description "Resistor")
      (fields (field (name "PUBLISHER") "Altium Limited"))
      (libsource (lib "_ROBOT") (part "Resistor"))
    )
    (comp (ref "RR12")
      (value "330")
      (footprint "R1206_N")
      (description "Resistor")
      (fields (field (name "PUBLISHER") "Altium Limited"))
      (libsource (lib "_ROBOT") (part "Resistor"))
    )
    (comp (ref "RR13")
      (value "330")
      (footprint "R1206_N")
      (description "Resistor")
      (fields (field (name "PUBLISHER") "Altium Limited"))
      (libsource (lib "_ROBOT") (part "Resistor"))
    )
    (comp (ref "RR14")
      (value "330")
      (footprint "R1206_N")
      (description "Resistor")
      (fields (field (name "PUBLISHER") "Altium Limited"))
      (libsource (lib "_ROBOT") (part "Resistor"))
    )
    (comp (ref "RR15")
      (value "330")
      (footprint "R1206_N")
      (description "Resistor")
      (fields (field (name "PUBLISHER") "Altium Limited"))
      (libsource (lib "_ROBOT") (part "Resistor"))
    )
    (comp (ref "RsdCS")
      (value "22")
      (footprint "R1206_N")
      (description "Resistor")
      (fields (field (name "PUBLISHER") "Altium Limited"))
      (libsource (lib "_ROBOT") (part "Resistor"))
    )
    (comp (ref "RsdMiso")
      (value "22")
      (footprint "R1206_N")
      (description "Resistor")
      (fields (field (name "PUBLISHER") "Altium Limited"))
      (libsource (lib "_ROBOT") (part "Resistor"))
    )
    (comp (ref "RsdMosi")
      (value "22")
      (footprint "R1206_N")
      (description "Resistor")
      (fields (field (name "PUBLISHER") "Altium Limited"))
      (libsource (lib "_ROBOT") (part "Resistor"))
    )
    (comp (ref "RsdSck")
      (value "22")
      (footprint "R1206_N")
      (description "Resistor")
      (fields (field (name "PUBLISHER") "Altium Limited"))
      (libsource (lib "_ROBOT") (part "Resistor"))
    )
    (comp (ref "Rsu1rx")
      (value "1k")
      (footprint "R1206_N")
      (description "Resistor")
      (fields (field (name "PUBLISHER") "Altium Limited"))
      (libsource (lib "_ROBOT") (part "Resistor"))
    )
    (comp (ref "RsU1tx")
      (value "100")
      (footprint "R1206_N")
      (description "Resistor")
      (fields (field (name "PUBLISHER") "Altium Limited"))
      (libsource (lib "_ROBOT") (part "Resistor"))
    )
    (comp (ref "RupWAmI")
      (value "0")
      (footprint "R1206_N")
      (description "Resistor")
      (fields (field (name "PUBLISHER") "Altium Limited"))
      (libsource (lib "_ROBOT") (part "Resistor"))
    )
    (comp (ref "STM32")
      (value "STM32F407VGT6")
      (footprint "STM-LQFP100_N")
      (fields (field (name "MANUFACTURER") "STMicroelectronics"))
      (libsource (lib "STMicroelectronics STM32 F4") (part "STM32F407VGT6"))
    )
    (comp (ref "TSOP0")
      (value "TSOP")
      (footprint "HDR1X3")
      (description "Header, 3-Pin")
      (fields (field (name "PUBLISHER") "Altium Limited"))
      (libsource (lib "Robot2010") (part "HDR1X3"))
    )
    (comp (ref "TSOP1")
      (value "TSOP")
      (footprint "HDR1X3")
      (description "Header, 3-Pin")
      (fields (field (name "PUBLISHER") "Altium Limited"))
      (libsource (lib "Robot2010") (part "HDR1X3"))
    )
    (comp (ref "TSOP2")
      (value "TSOP")
      (footprint "HDR1X3")
      (description "Header, 3-Pin")
      (fields (field (name "PUBLISHER") "Altium Limited"))
      (libsource (lib "Robot2010") (part "HDR1X3"))
    )
    (comp (ref "TSOP3")
      (value "TSOP")
      (footprint "HDR1X3")
      (description "Header, 3-Pin")
      (fields (field (name "PUBLISHER") "Altium Limited"))
      (libsource (lib "Robot2010") (part "HDR1X3"))
    )
    (comp (ref "TSOP4")
      (value "TSOP")
      (footprint "HDR1X3")
      (description "Header, 3-Pin")
      (fields (field (name "PUBLISHER") "Altium Limited"))
      (libsource (lib "Robot2010") (part "HDR1X3"))
    )
    (comp (ref "TSOP5")
      (value "TSOP")
      (footprint "HDR1X3")
      (description "Header, 3-Pin")
      (fields (field (name "PUBLISHER") "Altium Limited"))
      (libsource (lib "Robot2010") (part "HDR1X3"))
    )
    (comp (ref "TSOP6")
      (value "TSOP")
      (footprint "HDR1X3")
      (description "Header, 3-Pin")
      (fields (field (name "PUBLISHER") "Altium Limited"))
      (libsource (lib "Robot2010") (part "HDR1X3"))
    )
    (comp (ref "TSOP7")
      (value "TSOP")
      (footprint "HDR1X3")
      (description "Header, 3-Pin")
      (fields (field (name "PUBLISHER") "Altium Limited"))
      (libsource (lib "Robot2010") (part "HDR1X3"))
    )
    (comp (ref "TSOP8")
      (value "TSOP")
      (footprint "HDR1X3")
      (description "Header, 3-Pin")
      (fields (field (name "PUBLISHER") "Altium Limited"))
      (libsource (lib "Robot2010") (part "HDR1X3"))
    )
    (comp (ref "TSOP9")
      (value "TSOP")
      (footprint "HDR1X3")
      (description "Header, 3-Pin")
      (fields (field (name "PUBLISHER") "Altium Limited"))
      (libsource (lib "Robot2010") (part "HDR1X3"))
    )
    (comp (ref "TSOP10")
      (value "TSOP")
      (footprint "HDR1X3")
      (description "Header, 3-Pin")
      (fields (field (name "PUBLISHER") "Altium Limited"))
      (libsource (lib "Robot2010") (part "HDR1X3"))
    )
    (comp (ref "TSOP11")
      (value "TSOP")
      (footprint "HDR1X3")
      (description "Header, 3-Pin")
      (fields (field (name "PUBLISHER") "Altium Limited"))
      (libsource (lib "Robot2010") (part "HDR1X3"))
    )
    (comp (ref "TSOP12")
      (value "TSOP")
      (footprint "HDR1X3")
      (description "Header, 3-Pin")
      (fields (field (name "PUBLISHER") "Altium Limited"))
      (libsource (lib "Robot2010") (part "HDR1X3"))
    )
    (comp (ref "TSOP13")
      (value "TSOP")
      (footprint "HDR1X3")
      (description "Header, 3-Pin")
      (fields (field (name "PUBLISHER") "Altium Limited"))
      (libsource (lib "Robot2010") (part "HDR1X3"))
    )
    (comp (ref "TSOP14")
      (value "TSOP")
      (footprint "HDR1X3")
      (description "Header, 3-Pin")
      (fields (field (name "PUBLISHER") "Altium Limited"))
      (libsource (lib "Robot2010") (part "HDR1X3"))
    )
    (comp (ref "TSOP15")
      (value "TSOP")
      (footprint "HDR1X3")
      (description "Header, 3-Pin")
      (fields (field (name "PUBLISHER") "Altium Limited"))
      (libsource (lib "Robot2010") (part "HDR1X3"))
    )
    (comp (ref "UART")
      (value "BARRETTE4")
      (footprint "HDR1X4")
      (description "Header, 4-Pin")
      (fields (field (name "PUBLISHER") "Altium Limited"))
      (libsource (lib "Connecteur") (part "HDR1X4"))
    )
    (comp (ref "Ucan")
      (value "MCP2551-I/SN")
      (footprint "SO8_N")
      (description "High-Speed CAN Transceiver, 8-Pin SOIC, Industrial Temperature")
      (fields (field (name "PUBLISHER") "Damien Guitton"))
      (libsource (lib "Circuit intégré") (part "MCP2551-I/SN"))
    )
    (comp (ref "Ureg_3V")
      (value "MCP1826S-3302E/DB")
      (footprint "SOT223-4N")
      (description "1000 mA, Low Voltage, Low Quiescent Current LDO Regulator, 3-Pin SOT-223, Extended Temperature")
      (fields (field (name "PUBLISHER") "Altium Limited"))
      (libsource (lib "Microchip Power Mgt Line Regulator") (part "MCP1826S-3302E/DB"))
    )
    (comp (ref "USB")
      (value "USB_B_MINI")
      (footprint "USB_MICROAB_VERTICAL")
      (description "Connector; USB; Type B; miniature; Pin Spacing=0.8mm")
      (libsource (lib "DG_Connecteur") (part "USB_B_MINI"))
    )
    (comp (ref "USB_ESD")
      (value "USBDF01W5")
      (footprint "SOT353_N")
      (description "USB protection ESD")
      (libsource (lib "Circuit intégré") (part "USBDF01W5"))
    )
    (comp (ref "Uxbee") (value "XBee") (footprint "MODULE_XBEE") (libsource (lib "*") (part "XBee")))
    (comp (ref "V1")
      (value "Entretoise WURTH CMS")
      (footprint "ENTRETOISE_CMS")
      (description "Entretoise Wurth")
      (fields (field (name "PUBLISHER") "Damien Guitton"))
      (libsource (lib "_ROBOT") (part "Entretoise WURTH CMS"))
    )
    (comp (ref "V2")
      (value "Entretoise WURTH CMS")
      (footprint "ENTRETOISE_CMS")
      (description "Entretoise Wurth")
      (fields (field (name "PUBLISHER") "Damien Guitton"))
      (libsource (lib "_ROBOT") (part "Entretoise WURTH CMS"))
    )
    (comp (ref "V3")
      (value "Entretoise WURTH CMS")
      (footprint "ENTRETOISE_CMS")
      (description "Entretoise Wurth")
      (fields (field (name "PUBLISHER") "Damien Guitton"))
      (libsource (lib "_ROBOT") (part "Entretoise WURTH CMS"))
    )
    (comp (ref "V4")
      (value "Entretoise WURTH CMS")
      (footprint "ENTRETOISE_CMS")
      (description "Entretoise Wurth")
      (fields (field (name "PUBLISHER") "Damien Guitton"))
      (libsource (lib "_ROBOT") (part "Entretoise WURTH CMS"))
    )
    (comp (ref "Y1")
      (value "8 MHz")
      (footprint "HC49/4H_SMX")
      (description "Crystal Oscillator")
      (fields (field (name "PUBLISHER") "Altium Limited"))
      (libsource (lib "_ROBOT") (part "Quartz"))
    )
  )
  (nets
    (net (code "1") (name "/ANTENNA") (class "Default")
      (node (ref "Antenne_433") (pin "1") (pinfunction "1_1") (pintype "passive"))
      (node (ref "RC1240") (pin "9") (pinfunction "RF_9") (pintype "passive"))
    )
    (net (code "2") (name "/BlueGND") (class "Default")
      (node (ref "Qb") (pin "3") (pinfunction "D_3") (pintype "passive"))
      (node (ref "RB0") (pin "1") (pinfunction "1_1") (pintype "passive"))
      (node (ref "RB1") (pin "1") (pinfunction "1_1") (pintype "passive"))
      (node (ref "RB10") (pin "1") (pinfunction "1_1") (pintype "passive"))
      (node (ref "RB11") (pin "1") (pinfunction "1_1") (pintype "passive"))
      (node (ref "RB12") (pin "1") (pinfunction "1_1") (pintype "passive"))
      (node (ref "RB13") (pin "1") (pinfunction "1_1") (pintype "passive"))
      (node (ref "RB14") (pin "1") (pinfunction "1_1") (pintype "passive"))
      (node (ref "RB15") (pin "1") (pinfunction "1_1") (pintype "passive"))
      (node (ref "RB2") (pin "1") (pinfunction "1_1") (pintype "passive"))
      (node (ref "RB3") (pin "1") (pinfunction "1_1") (pintype "passive"))
      (node (ref "RB4") (pin "1") (pinfunction "1_1") (pintype "passive"))
      (node (ref "RB5") (pin "1") (pinfunction "1_1") (pintype "passive"))
      (node (ref "RB6") (pin "1") (pinfunction "1_1") (pintype "passive"))
      (node (ref "RB7") (pin "1") (pinfunction "1_1") (pintype "passive"))
      (node (ref "RB8") (pin "1") (pinfunction "1_1") (pintype "passive"))
      (node (ref "RB9") (pin "1") (pinfunction "1_1") (pintype "passive"))
    )
    (net (code "3") (name "/CANH") (class "Default")
      (node (ref "HE10") (pin "15") (pinfunction "15_15") (pintype "passive"))
      (node (ref "Ucan") (pin "7") (pinfunction "CANH_7") (pintype "bidirectional"))
    )
    (net (code "4") (name "/CANL") (class "Default")
      (node (ref "HE10") (pin "16") (pinfunction "16_16") (pintype "passive"))
      (node (ref "Ucan") (pin "6") (pinfunction "CANL_6") (pintype "bidirectional"))
    )
    (net (code "5") (name "/GreenGND") (class "Default")
      (node (ref "Qg") (pin "3") (pinfunction "D_3") (pintype "passive"))
      (node (ref "RG0") (pin "1") (pinfunction "1_1") (pintype "passive"))
      (node (ref "RG1") (pin "1") (pinfunction "1_1") (pintype "passive"))
      (node (ref "RG10") (pin "1") (pinfunction "1_1") (pintype "passive"))
      (node (ref "RG11") (pin "1") (pinfunction "1_1") (pintype "passive"))
      (node (ref "RG12") (pin "1") (pinfunction "1_1") (pintype "passive"))
      (node (ref "RG13") (pin "1") (pinfunction "1_1") (pintype "passive"))
      (node (ref "RG14") (pin "1") (pinfunction "1_1") (pintype "passive"))
      (node (ref "RG15") (pin "1") (pinfunction "1_1") (pintype "passive"))
      (node (ref "RG2") (pin "1") (pinfunction "1_1") (pintype "passive"))
      (node (ref "RG3") (pin "1") (pinfunction "1_1") (pintype "passive"))
      (node (ref "RG4") (pin "1") (pinfunction "1_1") (pintype "passive"))
      (node (ref "RG5") (pin "1") (pinfunction "1_1") (pintype "passive"))
      (node (ref "RG6") (pin "1") (pinfunction "1_1") (pintype "passive"))
      (node (ref "RG7") (pin "1") (pinfunction "1_1") (pintype "passive"))
      (node (ref "RG8") (pin "1") (pinfunction "1_1") (pintype "passive"))
      (node (ref "RG9") (pin "1") (pinfunction "1_1") (pintype "passive"))
    )
    (net (code "6") (name "/LEDS0") (class "Default")
      (node (ref "DB0") (pin "1") (pinfunction "A_1") (pintype "passive"))
      (node (ref "DG0") (pin "1") (pinfunction "A_1") (pintype "passive"))
      (node (ref "DR0") (pin "1") (pinfunction "A_1") (pintype "passive"))
      (node (ref "STM32") (pin "15") (pinfunction "PC0_15") (pintype "bidirectional"))
    )
    (net (code "7") (name "/LEDS1") (class "Default")
      (node (ref "DB1") (pin "1") (pinfunction "A_1") (pintype "passive"))
      (node (ref "DG1") (pin "1") (pinfunction "A_1") (pintype "passive"))
      (node (ref "DR1") (pin "1") (pinfunction "A_1") (pintype "passive"))
      (node (ref "STM32") (pin "16") (pinfunction "PC1_16") (pintype "bidirectional"))
    )
    (net (code "8") (name "/LEDS2") (class "Default")
      (node (ref "DB2") (pin "1") (pinfunction "A_1") (pintype "passive"))
      (node (ref "DG2") (pin "1") (pinfunction "A_1") (pintype "passive"))
      (node (ref "DR2") (pin "1") (pinfunction "A_1") (pintype "passive"))
      (node (ref "STM32") (pin "17") (pinfunction "PC2_17") (pintype "bidirectional"))
    )
    (net (code "9") (name "/LEDS3") (class "Default")
      (node (ref "DB3") (pin "1") (pinfunction "A_1") (pintype "passive"))
      (node (ref "DG3") (pin "1") (pinfunction "A_1") (pintype "passive"))
      (node (ref "DR3") (pin "1") (pinfunction "A_1") (pintype "passive"))
      (node (ref "STM32") (pin "18") (pinfunction "PC3_18") (pintype "bidirectional"))
    )
    (net (code "10") (name "/LEDS4") (class "Default")
      (node (ref "DB4") (pin "1") (pinfunction "A_1") (pintype "passive"))
      (node (ref "DG4") (pin "1") (pinfunction "A_1") (pintype "passive"))
      (node (ref "DR4") (pin "1") (pinfunction "A_1") (pintype "passive"))
      (node (ref "STM32") (pin "33") (pinfunction "PC4_33") (pintype "bidirectional"))
    )
    (net (code "11") (name "/LEDS5") (class "Default")
      (node (ref "DB5") (pin "1") (pinfunction "A_1") (pintype "passive"))
      (node (ref "DG5") (pin "1") (pinfunction "A_1") (pintype "passive"))
      (node (ref "DR5") (pin "1") (pinfunction "A_1") (pintype "passive"))
      (node (ref "STM32") (pin "34") (pinfunction "PC5_34") (pintype "bidirectional"))
    )
    (net (code "12") (name "/LEDS6") (class "Default")
      (node (ref "DB6") (pin "1") (pinfunction "A_1") (pintype "passive"))
      (node (ref "DG6") (pin "1") (pinfunction "A_1") (pintype "passive"))
      (node (ref "DR6") (pin "1") (pinfunction "A_1") (pintype "passive"))
      (node (ref "STM32") (pin "63") (pinfunction "PC6_63") (pintype "bidirectional"))
    )
    (net (code "13") (name "/LEDS7") (class "Default")
      (node (ref "DB7") (pin "1") (pinfunction "A_1") (pintype "passive"))
      (node (ref "DG7") (pin "1") (pinfunction "A_1") (pintype "passive"))
      (node (ref "DR7") (pin "1") (pinfunction "A_1") (pintype "passive"))
      (node (ref "STM32") (pin "64") (pinfunction "PC7_64") (pintype "bidirectional"))
    )
    (net (code "14") (name "/LEDS8") (class "Default")
      (node (ref "DB8") (pin "1") (pinfunction "A_1") (pintype "passive"))
      (node (ref "DG8") (pin "1") (pinfunction "A_1") (pintype "passive"))
      (node (ref "DR8") (pin "1") (pinfunction "A_1") (pintype "passive"))
      (node (ref "STM32") (pin "65") (pinfunction "PC8_65") (pintype "bidirectional"))
    )
    (net (code "15") (name "/LEDS9") (class "Default")
      (node (ref "DB9") (pin "1") (pinfunction "A_1") (pintype "passive"))
      (node (ref "DG9") (pin "1") (pinfunction "A_1") (pintype "passive"))
      (node (ref "DR9") (pin "1") (pinfunction "A_1") (pintype "passive"))
      (node (ref "STM32") (pin "66") (pinfunction "PC9_66") (pintype "bidirectional"))
    )
    (net (code "16") (name "/LEDS10") (class "Default")
      (node (ref "DB10") (pin "1") (pinfunction "A_1") (pintype "passive"))
      (node (ref "DG10") (pin "1") (pinfunction "A_1") (pintype "passive"))
      (node (ref "DR10") (pin "1") (pinfunction "A_1") (pintype "passive"))
      (node (ref "STM32") (pin "78") (pinfunction "PC10_78") (pintype "bidirectional"))
    )
    (net (code "17") (name "/LEDS11") (class "Default")
      (node (ref "DB11") (pin "1") (pinfunction "A_1") (pintype "passive"))
      (node (ref "DG11") (pin "1") (pinfunction "A_1") (pintype "passive"))
      (node (ref "DR11") (pin "1") (pinfunction "A_1") (pintype "passive"))
      (node (ref "STM32") (pin "79") (pinfunction "PC11_79") (pintype "bidirectional"))
    )
    (net (code "18") (name "/LEDS12") (class "Default")
      (node (ref "DB12") (pin "1") (pinfunction "A_1") (pintype "passive"))
      (node (ref "DG12") (pin "1") (pinfunction "A_1") (pintype "passive"))
      (node (ref "DR12") (pin "1") (pinfunction "A_1") (pintype "passive"))
      (node (ref "STM32") (pin "80") (pinfunction "PC12_80") (pintype "bidirectional"))
    )
    (net (code "19") (name "/LEDS13") (class "Default")
      (node (ref "DB13") (pin "1") (pinfunction "A_1") (pintype "passive"))
      (node (ref "DG13") (pin "1") (pinfunction "A_1") (pintype "passive"))
      (node (ref "DR13") (pin "1") (pinfunction "A_1") (pintype "passive"))
      (node (ref "STM32") (pin "7") (pinfunction "PC13_7") (pintype "bidirectional"))
    )
    (net (code "20") (name "/LEDS14") (class "Default")
      (node (ref "DB14") (pin "1") (pinfunction "A_1") (pintype "passive"))
      (node (ref "DG14") (pin "1") (pinfunction "A_1") (pintype "passive"))
      (node (ref "DR14") (pin "1") (pinfunction "A_1") (pintype "passive"))
      (node (ref "STM32") (pin "8") (pinfunction "PC14-OSC32_IN(PC14)_8") (pintype "bidirectional"))
    )
    (net (code "21") (name "/LEDS15") (class "Default")
      (node (ref "DB15") (pin "1") (pinfunction "A_1") (pintype "passive"))
      (node (ref "DG15") (pin "1") (pinfunction "A_1") (pintype "passive"))
      (node (ref "DR15") (pin "1") (pinfunction "A_1") (pintype "passive"))
      (node (ref "STM32") (pin "9") (pinfunction "PC15-OSC32_OUT(PC15)_9") (pintype "bidirectional"))
    )
    (net (code "22") (name "/PA0_BP") (class "Default")
      (node (ref "STM32") (pin "23") (pinfunction "PA0-WKUP(PA0)_23") (pintype "bidirectional"))
    )
    (net (code "23") (name "/PA1_WHO_AM_I") (class "Default")
      (node (ref "RdwnWAmI") (pin "2") (pinfunction "2_2") (pintype "passive"))
      (node (ref "RupWAmI") (pin "1") (pinfunction "1_1") (pintype "passive"))
      (node (ref "STM32") (pin "24") (pinfunction "PA1_24") (pintype "bidirectional"))
    )
    (net (code "24") (name "/PA2_U2TX_XBEE") (class "Default")
      (node (ref "STM32") (pin "25") (pinfunction "PA2_25") (pintype "bidirectional"))
      (node (ref "Uxbee") (pin "3") (pinfunction "RX_3") (pintype "output"))
    )
    (net (code "25") (name "/PA3_U2RX_XBEE") (class "Default")
      (node (ref "STM32") (pin "26") (pinfunction "PA3_26") (pintype "bidirectional"))
      (node (ref "Uxbee") (pin "2") (pinfunction "TX_2") (pintype "output"))
    )
    (net (code "26") (name "/PA4_XBEE_RESET") (class "Default")
      (node (ref "QXbee") (pin "1") (pinfunction "G_1") (pintype "passive"))
      (node (ref "RpXbee") (pin "1") (pinfunction "1_1") (pintype "passive"))
      (node (ref "STM32") (pin "29") (pinfunction "PA4_29") (pintype "bidirectional"))
    )
    (net (code "27") (name "/PA5_RF_RESET") (class "Default")
      (node (ref "QRF") (pin "1") (pinfunction "G_1") (pintype "passive"))
      (node (ref "RpRF") (pin "1") (pinfunction "1_1") (pintype "passive"))
      (node (ref "STM32") (pin "30") (pinfunction "PA5_30") (pintype "bidirectional"))
    )
    (net (code "28") (name "/PA6_RF_Config") (class "Default")
      (node (ref "RC1240") (pin "4") (pinfunction "CONFIG_4") (pintype "passive"))
      (node (ref "STM32") (pin "31") (pinfunction "PA6_31") (pintype "bidirectional"))
    )
    (net (code "29") (name "/PA8_LedSynchroR") (class "Default")
      (node (ref "RledSynchroR") (pin "2") (pinfunction "2_2") (pintype "passive"))
      (node (ref "STM32") (pin "67") (pinfunction "PA8_67") (pintype "bidirectional"))
    )
    (net (code "30") (name "/PA9_LedSynchroG") (class "Default")
      (node (ref "RledSynchroG") (pin "2") (pinfunction "2_2") (pintype "passive"))
      (node (ref "STM32") (pin "68") (pinfunction "PA9_68") (pintype "bidirectional"))
    )
    (net (code "31") (name "/PA10_USB_ID") (class "Default")
      (node (ref "STM32") (pin "69") (pinfunction "PA10_69") (pintype "bidirectional"))
      (node (ref "USB") (pin "4") (pinfunction "ID_4") (pintype "passive"))
    )
    (net (code "32") (name "/PA11_USB_DM") (class "Default")
      (node (ref "STM32") (pin "70") (pinfunction "PA11_70") (pintype "bidirectional"))
      (node (ref "USB_ESD") (pin "3") (pinfunction "D-in_3") (pintype "bidirectional"))
    )
    (net (code "33") (name "/PA12_USB_DP") (class "Default")
      (node (ref "STM32") (pin "71") (pinfunction "PA12_71") (pintype "bidirectional"))
      (node (ref "USB_ESD") (pin "1") (pinfunction "D+in_1") (pintype "bidirectional"))
    )
    (net (code "34") (name "/PB6_U1TX") (class "Default")
      (node (ref "RsU1tx") (pin "2") (pinfunction "2_2") (pintype "passive"))
      (node (ref "STM32") (pin "92") (pinfunction "PB6_92") (pintype "bidirectional"))
    )
    (net (code "35") (name "/PB7_U1RX") (class "Default")
      (node (ref "Cu1rx") (pin "2") (pinfunction "2_2") (pintype "passive"))
      (node (ref "RpuU1rx") (pin "1") (pinfunction "1_1") (pintype "passive"))
      (node (ref "Rsu1rx") (pin "1") (pinfunction "1_1") (pintype "passive"))
      (node (ref "STM32") (pin "93") (pinfunction "PB7_93") (pintype "bidirectional"))
    )
    (net (code "36") (name "/PB8_I_AM_READY") (class "Default")
      (node (ref "STM32") (pin "95") (pinfunction "PB8_95") (pintype "bidirectional"))
    )
    (net (code "37") (name "/PB10_U3TX_RF") (class "Default")
      (node (ref "RC1240") (pin "6") (pinfunction "RXD/SDA_6") (pintype "passive"))
      (node (ref "STM32") (pin "47") (pinfunction "PB10_47") (pintype "bidirectional"))
    )
    (net (code "38") (name "/PB11_U3RX_RF") (class "Default")
      (node (ref "RC1240") (pin "5") (pinfunction "TXD/SCL_5") (pintype "passive"))
      (node (ref "STM32") (pin "48") (pinfunction "PB11_48") (pintype "bidirectional"))
    )
    (net (code "39") (name "/PB12_SD_CS") (class "Default")
      (node (ref "RpudCs") (pin "2") (pinfunction "2_2") (pintype "passive"))
      (node (ref "RsdCS") (pin "1") (pinfunction "1_1") (pintype "passive"))
      (node (ref "STM32") (pin "51") (pinfunction "PB12_51") (pintype "bidirectional"))
    )
    (net (code "40") (name "/PB13_SD_SCK") (class "Default")
      (node (ref "RpudSck") (pin "1") (pinfunction "1_1") (pintype "passive"))
      (node (ref "RsdSck") (pin "1") (pinfunction "1_1") (pintype "passive"))
      (node (ref "STM32") (pin "52") (pinfunction "PB13_52") (pintype "bidirectional"))
    )
    (net (code "41") (name "/PB14_SD_MISO") (class "Default")
      (node (ref "RpudMiso") (pin "1") (pinfunction "1_1") (pintype "passive"))
      (node (ref "RsdMiso") (pin "1") (pinfunction "1_1") (pintype "passive"))
      (node (ref "STM32") (pin "53") (pinfunction "PB14_53") (pintype "bidirectional"))
    )
    (net (code "42") (name "/PB15_SD_MOSI") (class "Default")
      (node (ref "RpudMosi") (pin "2") (pinfunction "2_2") (pintype "passive"))
      (node (ref "RsdMosi") (pin "1") (pinfunction "1_1") (pintype "passive"))
      (node (ref "STM32") (pin "54") (pinfunction "PB15_54") (pintype "bidirectional"))
    )
    (net (code "43") (name "/PD0_CANRX") (class "Default")
      (node (ref "STM32") (pin "81") (pinfunction "PD0_81") (pintype "bidirectional"))
      (node (ref "Ucan") (pin "4") (pinfunction "RXD_4") (pintype "output"))
    )
    (net (code "44") (name "/PD1_CANTX") (class "Default")
      (node (ref "STM32") (pin "82") (pinfunction "PD1_82") (pintype "bidirectional"))
      (node (ref "Ucan") (pin "1") (pinfunction "TXD_1") (pintype "input"))
    )
    (net (code "45") (name "/PD2_LED_Green") (class "Default")
      (node (ref "Qg") (pin "1") (pinfunction "G_1") (pintype "passive"))
      (node (ref "RpdG") (pin "2") (pinfunction "2_2") (pintype "passive"))
      (node (ref "STM32") (pin "83") (pinfunction "PD2_83") (pintype "bidirectional"))
    )
    (net (code "46") (name "/PD3_LED_Red") (class "Default")
      (node (ref "Qr") (pin "1") (pinfunction "G_1") (pintype "passive"))
      (node (ref "RpdR") (pin "2") (pinfunction "2_2") (pintype "passive"))
      (node (ref "STM32") (pin "84") (pinfunction "PD3_84") (pintype "bidirectional"))
    )
    (net (code "47") (name "/PD4_LED_Blue") (class "Default")
      (node (ref "Qb") (pin "1") (pinfunction "G_1") (pintype "passive"))
      (node (ref "RpdB") (pin "2") (pinfunction "2_2") (pintype "passive"))
      (node (ref "STM32") (pin "85") (pinfunction "PD4_85") (pintype "bidirectional"))
    )
    (net (code "48") (name "/PD10_LED_RUN") (class "Default")
      (node (ref "RledRun") (pin "2") (pinfunction "2_2") (pintype "passive"))
      (node (ref "STM32") (pin "57") (pinfunction "PD10_57") (pintype "bidirectional"))
    )
    (net (code "49") (name "/PD15_LED_USER") (class "Default")
      (node (ref "RledUsr") (pin "2") (pinfunction "2_2") (pintype "passive"))
      (node (ref "STM32") (pin "62") (pinfunction "PD15_62") (pintype "bidirectional"))
    )
    (net (code "50") (name "/PROG_NRST") (class "Default")
      (node (ref "Cnrst") (pin "2") (pinfunction "2_2") (pintype "passive"))
      (node (ref "P1") (pin "5") (pinfunction "NRST_5") (pintype "passive"))
      (node (ref "Rnrst") (pin "1") (pinfunction "1_1") (pintype "passive"))
      (node (ref "STM32") (pin "14") (pinfunction "NRST_14") (pintype "bidirectional"))
    )
    (net (code "51") (name "/PROG_SWCLK") (class "Default")
      (node (ref "P1") (pin "2") (pinfunction "SWCLK_2") (pintype "passive"))
      (node (ref "STM32") (pin "76") (pinfunction "PA14(JTCK-SWCLK)_76") (pintype "bidirectional"))
    )
    (net (code "52") (name "/PROG_SWDIO") (class "Default")
      (node (ref "P1") (pin "4") (pinfunction "SWDIO_4") (pintype "passive"))
      (node (ref "STM32") (pin "72") (pinfunction "PA13(JTMS-SWDIO)_72") (pintype "bidirectional"))
    )
    (net (code "53") (name "/PROG_SWO") (class "Default")
      (node (ref "P1") (pin "6") (pinfunction "SWO_6") (pintype "passive"))
      (node (ref "STM32") (pin "89") (pinfunction "PB3(JTDO/TRACESWO)_89") (pintype "bidirectional"))
    )
    (net (code "54") (name "/RedGND") (class "Default")
      (node (ref "Qr") (pin "3") (pinfunction "D_3") (pintype "passive"))
      (node (ref "RR0") (pin "1") (pinfunction "1_1") (pintype "passive"))
      (node (ref "RR1") (pin "1") (pinfunction "1_1") (pintype "passive"))
      (node (ref "RR10") (pin "1") (pinfunction "1_1") (pintype "passive"))
      (node (ref "RR11") (pin "1") (pinfunction "1_1") (pintype "passive"))
      (node (ref "RR12") (pin "1") (pinfunction "1_1") (pintype "passive"))
      (node (ref "RR13") (pin "1") (pinfunction "1_1") (pintype "passive"))
      (node (ref "RR14") (pin "1") (pinfunction "1_1") (pintype "passive"))
      (node (ref "RR15") (pin "1") (pinfunction "1_1") (pintype "passive"))
      (node (ref "RR2") (pin "1") (pinfunction "1_1") (pintype "passive"))
      (node (ref "RR3") (pin "1") (pinfunction "1_1") (pintype "passive"))
      (node (ref "RR4") (pin "1") (pinfunction "1_1") (pintype "passive"))
      (node (ref "RR5") (pin "1") (pinfunction "1_1") (pintype "passive"))
      (node (ref "RR6") (pin "1") (pinfunction "1_1") (pintype "passive"))
      (node (ref "RR7") (pin "1") (pinfunction "1_1") (pintype "passive"))
      (node (ref "RR8") (pin "1") (pinfunction "1_1") (pintype "passive"))
      (node (ref "RR9") (pin "1") (pinfunction "1_1") (pintype "passive"))
    )
    (net (code "55") (name "/STR_RF_CONFIG") (class "Default")
      (node (ref "HE10") (pin "11") (pinfunction "11_11") (pintype "passive+no_connect"))
    )
    (net (code "56") (name "/STR_RF_RESET") (class "Default")
      (node (ref "HE10") (pin "10") (pinfunction "10_10") (pintype "passive+no_connect"))
    )
    (net (code "57") (name "/STR_RF_RX") (class "Default")
      (node (ref "HE10") (pin "12") (pinfunction "12_12") (pintype "passive+no_connect"))
    )
    (net (code "58") (name "/STR_RF_TX") (class "Default")
      (node (ref "HE10") (pin "9") (pinfunction "9_9") (pintype "passive+no_connect"))
    )
    (net (code "59") (name "/STR_SYNCHRO") (class "Default")
      (node (ref "HE10") (pin "13") (pinfunction "13_13") (pintype "passive+no_connect"))
    )
    (net (code "60") (name "/STR_XBEE_RESET") (class "Default")
      (node (ref "HE10") (pin "8") (pinfunction "8_8") (pintype "passive+no_connect"))
    )
    (net (code "61") (name "/STR_XBEE_RX") (class "Default")
      (node (ref "HE10") (pin "6") (pinfunction "6_6") (pintype "passive+no_connect"))
    )
    (net (code "62") (name "/STR_XBEE_TX") (class "Default")
      (node (ref "HE10") (pin "5") (pinfunction "5_5") (pintype "passive+no_connect"))
    )
    (net (code "63") (name "/TSOP0") (class "Default")
      (node (ref "Rp0") (pin "2") (pinfunction "2_2") (pintype "passive"))
      (node (ref "STM32") (pin "97") (pinfunction "PE0_97") (pintype "bidirectional"))
      (node (ref "TSOP0") (pin "1") (pinfunction "1_1") (pintype "passive"))
    )
    (net (code "64") (name "/TSOP1") (class "Default")
      (node (ref "Rp1") (pin "2") (pinfunction "2_2") (pintype "passive"))
      (node (ref "STM32") (pin "98") (pinfunction "PE1_98") (pintype "bidirectional"))
      (node (ref "TSOP1") (pin "1") (pinfunction "1_1") (pintype "passive"))
    )
    (net (code "65") (name "/TSOP2") (class "Default")
      (node (ref "Rp2") (pin "2") (pinfunction "2_2") (pintype "passive"))
      (node (ref "STM32") (pin "1") (pinfunction "PE2_1") (pintype "bidirectional"))
      (node (ref "TSOP2") (pin "1") (pinfunction "1_1") (pintype "passive"))
    )
    (net (code "66") (name "/TSOP3") (class "Default")
      (node (ref "Rp3") (pin "2") (pinfunction "2_2") (pintype "passive"))
      (node (ref "STM32") (pin "2") (pinfunction "PE3_2") (pintype "bidirectional"))
      (node (ref "TSOP3") (pin "1") (pinfunction "1_1") (pintype "passive"))
    )
    (net (code "67") (name "/TSOP4") (class "Default")
      (node (ref "Rp4") (pin "2") (pinfunction "2_2") (pintype "passive"))
      (node (ref "STM32") (pin "3") (pinfunction "PE4_3") (pintype "bidirectional"))
      (node (ref "TSOP4") (pin "1") (pinfunction "1_1") (pintype "passive"))
    )
    (net (code "68") (name "/TSOP5") (class "Default")
      (node (ref "Rp5") (pin "2") (pinfunction "2_2") (pintype "passive"))
      (node (ref "STM32") (pin "4") (pinfunction "PE5_4") (pintype "bidirectional"))
      (node (ref "TSOP5") (pin "1") (pinfunction "1_1") (pintype "passive"))
    )
    (net (code "69") (name "/TSOP6") (class "Default")
      (node (ref "Rp6") (pin "2") (pinfunction "2_2") (pintype "passive"))
      (node (ref "STM32") (pin "5") (pinfunction "PE6_5") (pintype "bidirectional"))
      (node (ref "TSOP6") (pin "1") (pinfunction "1_1") (pintype "passive"))
    )
    (net (code "70") (name "/TSOP7") (class "Default")
      (node (ref "Rp7") (pin "2") (pinfunction "2_2") (pintype "passive"))
      (node (ref "STM32") (pin "38") (pinfunction "PE7_38") (pintype "bidirectional"))
      (node (ref "TSOP7") (pin "1") (pinfunction "1_1") (pintype "passive"))
    )
    (net (code "71") (name "/TSOP8") (class "Default")
      (node (ref "Rp8") (pin "2") (pinfunction "2_2") (pintype "passive"))
      (node (ref "STM32") (pin "39") (pinfunction "PE8_39") (pintype "bidirectional"))
      (node (ref "TSOP8") (pin "1") (pinfunction "1_1") (pintype "passive"))
    )
    (net (code "72") (name "/TSOP9") (class "Default")
      (node (ref "Rp9") (pin "2") (pinfunction "2_2") (pintype "passive"))
      (node (ref "STM32") (pin "40") (pinfunction "PE9_40") (pintype "bidirectional"))
      (node (ref "TSOP9") (pin "1") (pinfunction "1_1") (pintype "passive"))
    )
    (net (code "73") (name "/TSOP10") (class "Default")
      (node (ref "Rp10") (pin "2") (pinfunction "2_2") (pintype "passive"))
      (node (ref "STM32") (pin "41") (pinfunction "PE10_41") (pintype "bidirectional"))
      (node (ref "TSOP10") (pin "1") (pinfunction "1_1") (pintype "passive"))
    )
    (net (code "74") (name "/TSOP11") (class "Default")
      (node (ref "Rp11") (pin "2") (pinfunction "2_2") (pintype "passive"))
      (node (ref "STM32") (pin "42") (pinfunction "PE11_42") (pintype "bidirectional"))
      (node (ref "TSOP11") (pin "1") (pinfunction "1_1") (pintype "passive"))
    )
    (net (code "75") (name "/TSOP12") (class "Default")
      (node (ref "Rp12") (pin "2") (pinfunction "2_2") (pintype "passive"))
      (node (ref "STM32") (pin "43") (pinfunction "PE12_43") (pintype "bidirectional"))
      (node (ref "TSOP12") (pin "1") (pinfunction "1_1") (pintype "passive"))
    )
    (net (code "76") (name "/TSOP13") (class "Default")
      (node (ref "Rp13") (pin "2") (pinfunction "2_2") (pintype "passive"))
      (node (ref "STM32") (pin "44") (pinfunction "PE13_44") (pintype "bidirectional"))
      (node (ref "TSOP13") (pin "1") (pinfunction "1_1") (pintype "passive"))
    )
    (net (code "77") (name "/TSOP14") (class "Default")
      (node (ref "Rp14") (pin "2") (pinfunction "2_2") (pintype "passive"))
      (node (ref "STM32") (pin "45") (pinfunction "PE14_45") (pintype "bidirectional"))
      (node (ref "TSOP14") (pin "1") (pinfunction "1_1") (pintype "passive"))
    )
    (net (code "78") (name "/TSOP15") (class "Default")
      (node (ref "Rp15") (pin "2") (pinfunction "2_2") (pintype "passive"))
      (node (ref "STM32") (pin "46") (pinfunction "PE15_46") (pintype "bidirectional"))
      (node (ref "TSOP15") (pin "1") (pinfunction "1_1") (pintype "passive"))
    )
    (net (code "79") (name "3V") (class "Default")
      (node (ref "HE10") (pin "3") (pinfunction "3_3") (pintype "passive"))
    )
    (net (code "80") (name "3V3") (class "Default")
      (node (ref "Cd0") (pin "2") (pinfunction "2_2") (pintype "passive"))
      (node (ref "Cd1") (pin "2") (pinfunction "2_2") (pintype "passive"))
      (node (ref "Cd1SD") (pin "2") (pinfunction "2_2") (pintype "passive"))
      (node (ref "Cd2") (pin "2") (pinfunction "2_2") (pintype "passive"))
      (node (ref "Cd2SD") (pin "2") (pinfunction "2_2") (pintype "passive"))
      (node (ref "Cd3") (pin "2") (pinfunction "2_2") (pintype "passive"))
      (node (ref "Cd3V_1") (pin "2") (pinfunction "2_2") (pintype "passive"))
      (node (ref "Cd4") (pin "2") (pinfunction "2_2") (pintype "passive"))
      (node (ref "Cd5") (pin "2") (pinfunction "2_2") (pintype "passive"))
      (node (ref "Cd6") (pin "2") (pinfunction "2_2") (pintype "passive"))
      (node (ref "Cd7") (pin "2") (pinfunction "2_2") (pintype "passive"))
      (node (ref "Cd8") (pin "2") (pinfunction "2_2") (pintype "passive"))
      (node (ref "Cd9") (pin "2") (pinfunction "2_2") (pintype "passive"))
      (node (ref "Cd_Xb_1") (pin "2") (pinfunction "2_2") (pintype "passive"))
      (node (ref "Cd_Xb_2") (pin "2") (pinfunction "2_2") (pintype "passive"))
      (node (ref "MICRO_SD") (pin "4") (pinfunction "VDD_4") (pintype "passive"))
      (node (ref "P1") (pin "1") (pinfunction "Vdd_Target_1") (pintype "passive"))
      (node (ref "Rnrst") (pin "2") (pinfunction "2_2") (pintype "passive"))
      (node (ref "RpuU1rx") (pin "2") (pinfunction "2_2") (pintype "passive"))
      (node (ref "RpuU1tx") (pin "2") (pinfunction "2_2") (pintype "passive"))
      (node (ref "RpudCs") (pin "1") (pinfunction "1_1") (pintype "passive"))
      (node (ref "RpudMiso") (pin "2") (pinfunction "2_2") (pintype "passive"))
      (node (ref "RpudMosi") (pin "1") (pinfunction "1_1") (pintype "passive"))
      (node (ref "RpudSck") (pin "2") (pinfunction "2_2") (pintype "passive"))
      (node (ref "RupWAmI") (pin "2") (pinfunction "2_2") (pintype "passive"))
      (node (ref "STM32") (pin "100") (pinfunction "VDD_100") (pintype "power_in"))
      (node (ref "STM32") (pin "11") (pinfunction "VDD_11") (pintype "power_in"))
      (node (ref "STM32") (pin "19") (pinfunction "VDD_19") (pintype "power_in"))
      (node (ref "STM32") (pin "21") (pinfunction "VREF+_21") (pintype "power_in"))
      (node (ref "STM32") (pin "22") (pinfunction "VDDA_22") (pintype "power_in"))
      (node (ref "STM32") (pin "28") (pinfunction "VDD_28") (pintype "power_in"))
      (node (ref "STM32") (pin "50") (pinfunction "VDD_50") (pintype "power_in"))
      (node (ref "STM32") (pin "6") (pinfunction "VBAT_6") (pintype "power_in"))
      (node (ref "STM32") (pin "75") (pinfunction "VDD_75") (pintype "power_in"))
      (node (ref "Ureg_3V") (pin "3") (pinfunction "VOUT_3") (pintype "power_in"))
      (node (ref "Uxbee") (pin "1") (pinfunction "VCC_1") (pintype "output"))
    )
    (net (code "81") (name "5V") (class "Default")
      (node (ref "Cd") (pin "2") (pinfunction "2_2") (pintype "passive"))
      (node (ref "CdCan1") (pin "2") (pinfunction "2_2") (pintype "passive"))
      (node (ref "CdCan2") (pin "2") (pinfunction "2_2") (pintype "passive"))
      (node (ref "CdUsb") (pin "1") (pinfunction "1_1") (pintype "passive"))
      (node (ref "Dz5V1") (pin "2") (pinfunction "K_2") (pintype "passive"))
      (node (ref "RC1240") (pin "12") (pinfunction "ON/OFF_12") (pintype "passive"))
      (node (ref "RC1240") (pin "13") (pinfunction "VCC_13") (pintype "passive"))
      (node (ref "Rf0") (pin "1") (pinfunction "1_1") (pintype "passive"))
      (node (ref "Rf1") (pin "1") (pinfunction "1_1") (pintype "passive"))
      (node (ref "Rf10") (pin "1") (pinfunction "1_1") (pintype "passive"))
      (node (ref "Rf11") (pin "1") (pinfunction "1_1") (pintype "passive"))
      (node (ref "Rf12") (pin "1") (pinfunction "1_1") (pintype "passive"))
      (node (ref "Rf13") (pin "1") (pinfunction "1_1") (pintype "passive"))
      (node (ref "Rf14") (pin "1") (pinfunction "1_1") (pintype "passive"))
      (node (ref "Rf15") (pin "1") (pinfunction "1_1") (pintype "passive"))
      (node (ref "Rf2") (pin "1") (pinfunction "1_1") (pintype "passive"))
      (node (ref "Rf3") (pin "1") (pinfunction "1_1") (pintype "passive"))
      (node (ref "Rf4") (pin "1") (pinfunction "1_1") (pintype "passive"))
      (node (ref "Rf5") (pin "1") (pinfunction "1_1") (pintype "passive"))
      (node (ref "Rf6") (pin "1") (pinfunction "1_1") (pintype "passive"))
      (node (ref "Rf7") (pin "1") (pinfunction "1_1") (pintype "passive"))
      (node (ref "Rf8") (pin "1") (pinfunction "1_1") (pintype "passive"))
      (node (ref "Rf9") (pin "1") (pinfunction "1_1") (pintype "passive"))
      (node (ref "Rp") (pin "2") (pinfunction "2_2") (pintype "passive"))
      (node (ref "Rp0") (pin "1") (pinfunction "1_1") (pintype "passive"))
      (node (ref "Rp1") (pin "1") (pinfunction "1_1") (pintype "passive"))
      (node (ref "Rp10") (pin "1") (pinfunction "1_1") (pintype "passive"))
      (node (ref "Rp11") (pin "1") (pinfunction "1_1") (pintype "passive"))
      (node (ref "Rp12") (pin "1") (pinfunction "1_1") (pintype "passive"))
      (node (ref "Rp13") (pin "1") (pinfunction "1_1") (pintype "passive"))
      (node (ref "Rp14") (pin "1") (pinfunction "1_1") (pintype "passive"))
      (node (ref "Rp15") (pin "1") (pinfunction "1_1") (pintype "passive"))
      (node (ref "Rp2") (pin "1") (pinfunction "1_1") (pintype "passive"))
      (node (ref "Rp3") (pin "1") (pinfunction "1_1") (pintype "passive"))
      (node (ref "Rp4") (pin "1") (pinfunction "1_1") (pintype "passive"))
      (node (ref "Rp5") (pin "1") (pinfunction "1_1") (pintype "passive"))
      (node (ref "Rp6") (pin "1") (pinfunction "1_1") (pintype "passive"))
      (node (ref "Rp7") (pin "1") (pinfunction "1_1") (pintype "passive"))
      (node (ref "Rp8") (pin "1") (pinfunction "1_1") (pintype "passive"))
      (node (ref "Rp9") (pin "1") (pinfunction "1_1") (pintype "passive"))
      (node (ref "UART") (pin "1") (pinfunction "1_1") (pintype "passive"))
      (node (ref "USB") (pin "1") (pinfunction "V_Bus_1") (pintype "passive"))
      (node (ref "Ucan") (pin "3") (pinfunction "VDD_3") (pintype "power_in"))
      (node (ref "Ureg_3V") (pin "1") (pinfunction "VIN_1") (pintype "power_in"))
    )
    (net (code "82") (name "5Vin") (class "Default")
      (node (ref "HE10") (pin "2") (pinfunction "2_2") (pintype "passive"))
      (node (ref "Rp") (pin "1") (pinfunction "1_1") (pintype "passive"))
    )
    (net (code "83") (name "GND") (class "Default")
      (node (ref "C46") (pin "1") (pinfunction "1_1") (pintype "passive"))
      (node (ref "C47") (pin "1") (pinfunction "1_1") (pintype "passive"))
      (node (ref "C49") (pin "1") (pinfunction "1_1") (pintype "passive"))
      (node (ref "C50") (pin "1") (pinfunction "1_1") (pintype "passive"))
      (node (ref "Cd") (pin "1") (pinfunction "1_1") (pintype "passive"))
      (node (ref "Cd0") (pin "1") (pinfunction "1_1") (pintype "passive"))
      (node (ref "Cd1") (pin "1") (pinfunction "1_1") (pintype "passive"))
      (node (ref "Cd1SD") (pin "1") (pinfunction "1_1") (pintype "passive"))
      (node (ref "Cd2") (pin "1") (pinfunction "1_1") (pintype "passive"))
      (node (ref "Cd2SD") (pin "1") (pinfunction "1_1") (pintype "passive"))
      (node (ref "Cd3") (pin "1") (pinfunction "1_1") (pintype "passive"))
      (node (ref "Cd3V_1") (pin "1") (pinfunction "1_1") (pintype "passive"))
      (node (ref "Cd4") (pin "1") (pinfunction "1_1") (pintype "passive"))
      (node (ref "Cd5") (pin "1") (pinfunction "1_1") (pintype "passive"))
      (node (ref "Cd6") (pin "1") (pinfunction "1_1") (pintype "passive"))
      (node (ref "Cd7") (pin "1") (pinfunction "1_1") (pintype "passive"))
      (node (ref "Cd8") (pin "1") (pinfunction "1_1") (pintype "passive"))
      (node (ref "Cd9") (pin "1") (pinfunction "1_1") (pintype "passive"))
      (node (ref "CdCan1") (pin "1") (pinfunction "1_1") (pintype "passive"))
      (node (ref "CdCan2") (pin "1") (pinfunction "1_1") (pintype "passive"))
      (node (ref "CdUsb") (pin "2") (pinfunction "2_2") (pintype "passive"))
      (node (ref "Cd_Xb_1") (pin "1") (pinfunction "1_1") (pintype "passive"))
      (node (ref "Cd_Xb_2") (pin "1") (pinfunction "1_1") (pintype "passive"))
      (node (ref "Cf0") (pin "1") (pinfunction "1_1") (pintype "passive"))
      (node (ref "Cf1") (pin "1") (pinfunction "1_1") (pintype "passive"))
      (node (ref "Cf10") (pin "1") (pinfunction "1_1") (pintype "passive"))
      (node (ref "Cf11") (pin "1") (pinfunction "1_1") (pintype "passive"))
      (node (ref "Cf12") (pin "1") (pinfunction "1_1") (pintype "passive"))
      (node (ref "Cf13") (pin "1") (pinfunction "1_1") (pintype "passive"))
      (node (ref "Cf14") (pin "1") (pinfunction "1_1") (pintype "passive"))
      (node (ref "Cf15") (pin "1") (pinfunction "1_1") (pintype "passive"))
      (node (ref "Cf2") (pin "1") (pinfunction "1_1") (pintype "passive"))
      (node (ref "Cf3") (pin "1") (pinfunction "1_1") (pintype "passive"))
      (node (ref "Cf4") (pin "1") (pinfunction "1_1") (pintype "passive"))
      (node (ref "Cf5") (pin "1") (pinfunction "1_1") (pintype "passive"))
      (node (ref "Cf6") (pin "1") (pinfunction "1_1") (pintype "passive"))
      (node (ref "Cf7") (pin "1") (pinfunction "1_1") (pintype "passive"))
      (node (ref "Cf8") (pin "1") (pinfunction "1_1") (pintype "passive"))
      (node (ref "Cf9") (pin "1") (pinfunction "1_1") (pintype "passive"))
      (node (ref "Cnrst") (pin "1") (pinfunction "1_1") (pintype "passive"))
      (node (ref "Cu1rx") (pin "1") (pinfunction "1_1") (pintype "passive"))
      (node (ref "Dz5V1") (pin "1") (pinfunction "A_1") (pintype "passive"))
      (node (ref "HE10") (pin "1") (pinfunction "1_1") (pintype "passive"))
      (node (ref "HE10") (pin "4") (pinfunction "4_4") (pintype "passive"))
      (node (ref "LedRun") (pin "2") (pinfunction "K_2") (pintype "passive"))
      (node (ref "LedSyncG") (pin "2") (pinfunction "K_2") (pintype "passive"))
      (node (ref "LedSyncR") (pin "2") (pinfunction "K_2") (pintype "passive"))
      (node (ref "LedUsr") (pin "2") (pinfunction "K_2") (pintype "passive"))
      (node (ref "MICRO_SD") (pin "0") (pinfunction "CAP_0") (pintype "passive"))
      (node (ref "MICRO_SD") (pin "6") (pinfunction "VSS_6") (pintype "passive"))
      (node (ref "MICRO_SD") (pin "9") (pinfunction "Nail_Gnd_9") (pintype "passive"))
      (node (ref "P1") (pin "3") (pinfunction "GND_3") (pintype "passive"))
      (node (ref "QRF") (pin "2") (pinfunction "S_2") (pintype "passive"))
      (node (ref "QXbee") (pin "2") (pinfunction "S_2") (pintype "passive"))
      (node (ref "Qb") (pin "2") (pinfunction "S_2") (pintype "passive"))
      (node (ref "Qg") (pin "2") (pinfunction "S_2") (pintype "passive"))
      (node (ref "Qr") (pin "2") (pinfunction "S_2") (pintype "passive"))
      (node (ref "RC1240") (pin "1") (pinfunction "GND_1") (pintype "passive"))
      (node (ref "RC1240") (pin "10") (pinfunction "GND_10") (pintype "passive"))
      (node (ref "RC1240") (pin "14") (pinfunction "GND_14") (pintype "passive"))
      (node (ref "RC1240") (pin "7") (pinfunction "GND_7") (pintype "passive"))
      (node (ref "RC1240") (pin "8") (pinfunction "GND_8") (pintype "passive"))
      (node (ref "RdwnWAmI") (pin "1") (pinfunction "1_1") (pintype "passive"))
      (node (ref "RpRF") (pin "2") (pinfunction "2_2") (pintype "passive"))
      (node (ref "RpXbee") (pin "2") (pinfunction "2_2") (pintype "passive"))
      (node (ref "RpdB") (pin "1") (pinfunction "1_1") (pintype "passive"))
      (node (ref "RpdG") (pin "1") (pinfunction "1_1") (pintype "passive"))
      (node (ref "RpdR") (pin "1") (pinfunction "1_1") (pintype "passive"))
      (node (ref "STM32") (pin "10") (pinfunction "VSS_10") (pintype "power_in"))
      (node (ref "STM32") (pin "20") (pinfunction "VSSA_20") (pintype "power_in"))
      (node (ref "STM32") (pin "27") (pinfunction "VSS_27") (pintype "power_in"))
      (node (ref "STM32") (pin "74") (pinfunction "VSS_74") (pintype "power_in"))
      (node (ref "STM32") (pin "94") (pinfunction "BOOT0_94") (pintype "input"))
      (node (ref "STM32") (pin "99") (pinfunction "VSS_99") (pintype "power_in"))
      (node (ref "TSOP0") (pin "2") (pinfunction "2_2") (pintype "passive"))
      (node (ref "TSOP1") (pin "2") (pinfunction "2_2") (pintype "passive"))
      (node (ref "TSOP10") (pin "2") (pinfunction "2_2") (pintype "passive"))
      (node (ref "TSOP11") (pin "2") (pinfunction "2_2") (pintype "passive"))
      (node (ref "TSOP12") (pin "2") (pinfunction "2_2") (pintype "passive"))
      (node (ref "TSOP13") (pin "2") (pinfunction "2_2") (pintype "passive"))
      (node (ref "TSOP14") (pin "2") (pinfunction "2_2") (pintype "passive"))
      (node (ref "TSOP15") (pin "2") (pinfunction "2_2") (pintype "passive"))
      (node (ref "TSOP2") (pin "2") (pinfunction "2_2") (pintype "passive"))
      (node (ref "TSOP3") (pin "2") (pinfunction "2_2") (pintype "passive"))
      (node (ref "TSOP4") (pin "2") (pinfunction "2_2") (pintype "passive"))
      (node (ref "TSOP5") (pin "2") (pinfunction "2_2") (pintype "passive"))
      (node (ref "TSOP6") (pin "2") (pinfunction "2_2") (pintype "passive"))
      (node (ref "TSOP7") (pin "2") (pinfunction "2_2") (pintype "passive"))
      (node (ref "TSOP8") (pin "2") (pinfunction "2_2") (pintype "passive"))
      (node (ref "TSOP9") (pin "2") (pinfunction "2_2") (pintype "passive"))
      (node (ref "UART") (pin "4") (pinfunction "4_4") (pintype "passive"))
      (node (ref "USB") (pin "5") (pinfunction "GND_5") (pintype "passive"))
      (node (ref "USB") (pin "6") (pinfunction "Blindage_6") (pintype "passive"))
      (node (ref "USB_ESD") (pin "2") (pinfunction "GND_2") (pintype "power_in"))
      (node (ref "Ucan") (pin "2") (pinfunction "VSS_2") (pintype "power_in"))
      (node (ref "Ucan") (pin "8") (pinfunction "RS_8") (pintype "input"))
      (node (ref "Ureg_3V") (pin "2") (pinfunction "GND_2") (pintype "power_in"))
      (node (ref "Ureg_3V") (pin "4") (pinfunction "GND_4") (pintype "power_in"))
      (node (ref "Uxbee") (pin "10") (pinfunction "GND_10") (pintype "output"))
      (node (ref "V1") (pin "1") (pinfunction "1_1") (pintype "passive"))
      (node (ref "V2") (pin "1") (pinfunction "1_1") (pintype "passive"))
      (node (ref "V3") (pin "1") (pinfunction "1_1") (pintype "passive"))
      (node (ref "V4") (pin "1") (pinfunction "1_1") (pintype "passive"))
    )
    (net (code "84") (name "Net-(Cf0-Pad2)") (class "Default")
      (node (ref "Cf0") (pin "2") (pinfunction "2_2") (pintype "passive"))
      (node (ref "Rf0") (pin "2") (pinfunction "2_2") (pintype "passive"))
      (node (ref "TSOP0") (pin "3") (pinfunction "3_3") (pintype "passive"))
    )
    (net (code "85") (name "Net-(Cf1-Pad2)") (class "Default")
      (node (ref "Cf1") (pin "2") (pinfunction "2_2") (pintype "passive"))
      (node (ref "Rf1") (pin "2") (pinfunction "2_2") (pintype "passive"))
      (node (ref "TSOP1") (pin "3") (pinfunction "3_3") (pintype "passive"))
    )
    (net (code "86") (name "Net-(Cf2-Pad2)") (class "Default")
      (node (ref "Cf2") (pin "2") (pinfunction "2_2") (pintype "passive"))
      (node (ref "Rf2") (pin "2") (pinfunction "2_2") (pintype "passive"))
      (node (ref "TSOP2") (pin "3") (pinfunction "3_3") (pintype "passive"))
    )
    (net (code "87") (name "Net-(Cf3-Pad2)") (class "Default")
      (node (ref "Cf3") (pin "2") (pinfunction "2_2") (pintype "passive"))
      (node (ref "Rf3") (pin "2") (pinfunction "2_2") (pintype "passive"))
      (node (ref "TSOP3") (pin "3") (pinfunction "3_3") (pintype "passive"))
    )
    (net (code "88") (name "Net-(Cf4-Pad2)") (class "Default")
      (node (ref "Cf4") (pin "2") (pinfunction "2_2") (pintype "passive"))
      (node (ref "Rf4") (pin "2") (pinfunction "2_2") (pintype "passive"))
      (node (ref "TSOP4") (pin "3") (pinfunction "3_3") (pintype "passive"))
    )
    (net (code "89") (name "Net-(Cf5-Pad2)") (class "Default")
      (node (ref "Cf5") (pin "2") (pinfunction "2_2") (pintype "passive"))
      (node (ref "Rf5") (pin "2") (pinfunction "2_2") (pintype "passive"))
      (node (ref "TSOP5") (pin "3") (pinfunction "3_3") (pintype "passive"))
    )
    (net (code "90") (name "Net-(Cf6-Pad2)") (class "Default")
      (node (ref "Cf6") (pin "2") (pinfunction "2_2") (pintype "passive"))
      (node (ref "Rf6") (pin "2") (pinfunction "2_2") (pintype "passive"))
      (node (ref "TSOP6") (pin "3") (pinfunction "3_3") (pintype "passive"))
    )
    (net (code "91") (name "Net-(Cf7-Pad2)") (class "Default")
      (node (ref "Cf7") (pin "2") (pinfunction "2_2") (pintype "passive"))
      (node (ref "Rf7") (pin "2") (pinfunction "2_2") (pintype "passive"))
      (node (ref "TSOP7") (pin "3") (pinfunction "3_3") (pintype "passive"))
    )
    (net (code "92") (name "Net-(Cf8-Pad2)") (class "Default")
      (node (ref "Cf8") (pin "2") (pinfunction "2_2") (pintype "passive"))
      (node (ref "Rf8") (pin "2") (pinfunction "2_2") (pintype "passive"))
      (node (ref "TSOP8") (pin "3") (pinfunction "3_3") (pintype "passive"))
    )
    (net (code "93") (name "Net-(Cf9-Pad2)") (class "Default")
      (node (ref "Cf9") (pin "2") (pinfunction "2_2") (pintype "passive"))
      (node (ref "Rf9") (pin "2") (pinfunction "2_2") (pintype "passive"))
      (node (ref "TSOP9") (pin "3") (pinfunction "3_3") (pintype "passive"))
    )
    (net (code "94") (name "Net-(Cf10-Pad2)") (class "Default")
      (node (ref "Cf10") (pin "2") (pinfunction "2_2") (pintype "passive"))
      (node (ref "Rf10") (pin "2") (pinfunction "2_2") (pintype "passive"))
      (node (ref "TSOP10") (pin "3") (pinfunction "3_3") (pintype "passive"))
    )
    (net (code "95") (name "Net-(Cf11-Pad2)") (class "Default")
      (node (ref "Cf11") (pin "2") (pinfunction "2_2") (pintype "passive"))
      (node (ref "Rf11") (pin "2") (pinfunction "2_2") (pintype "passive"))
      (node (ref "TSOP11") (pin "3") (pinfunction "3_3") (pintype "passive"))
    )
    (net (code "96") (name "Net-(Cf12-Pad2)") (class "Default")
      (node (ref "Cf12") (pin "2") (pinfunction "2_2") (pintype "passive"))
      (node (ref "Rf12") (pin "2") (pinfunction "2_2") (pintype "passive"))
      (node (ref "TSOP12") (pin "3") (pinfunction "3_3") (pintype "passive"))
    )
    (net (code "97") (name "Net-(Cf13-Pad2)") (class "Default")
      (node (ref "Cf13") (pin "2") (pinfunction "2_2") (pintype "passive"))
      (node (ref "Rf13") (pin "2") (pinfunction "2_2") (pintype "passive"))
      (node (ref "TSOP13") (pin "3") (pinfunction "3_3") (pintype "passive"))
    )
    (net (code "98") (name "Net-(Cf14-Pad2)") (class "Default")
      (node (ref "Cf14") (pin "2") (pinfunction "2_2") (pintype "passive"))
      (node (ref "Rf14") (pin "2") (pinfunction "2_2") (pintype "passive"))
      (node (ref "TSOP14") (pin "3") (pinfunction "3_3") (pintype "passive"))
    )
    (net (code "99") (name "Net-(Cf15-Pad2)") (class "Default")
      (node (ref "Cf15") (pin "2") (pinfunction "2_2") (pintype "passive"))
      (node (ref "Rf15") (pin "2") (pinfunction "2_2") (pintype "passive"))
      (node (ref "TSOP15") (pin "3") (pinfunction "3_3") (pintype "passive"))
    )
    (net (code "100") (name "Net-(DB0-K)") (class "Default")
      (node (ref "DB0") (pin "2") (pinfunction "K_2") (pintype "passive"))
      (node (ref "RB0") (pin "2") (pinfunction "2_2") (pintype "passive"))
    )
    (net (code "101") (name "Net-(DB1-K)") (class "Default")
      (node (ref "DB1") (pin "2") (pinfunction "K_2") (pintype "passive"))
      (node (ref "RB1") (pin "2") (pinfunction "2_2") (pintype "passive"))
    )
    (net (code "102") (name "Net-(DB2-K)") (class "Default")
      (node (ref "DB2") (pin "2") (pinfunction "K_2") (pintype "passive"))
      (node (ref "RB2") (pin "2") (pinfunction "2_2") (pintype "passive"))
    )
    (net (code "103") (name "Net-(DB3-K)") (class "Default")
      (node (ref "DB3") (pin "2") (pinfunction "K_2") (pintype "passive"))
      (node (ref "RB3") (pin "2") (pinfunction "2_2") (pintype "passive"))
    )
    (net (code "104") (name "Net-(DB4-K)") (class "Default")
      (node (ref "DB4") (pin "2") (pinfunction "K_2") (pintype "passive"))
      (node (ref "RB4") (pin "2") (pinfunction "2_2") (pintype "passive"))
    )
    (net (code "105") (name "Net-(DB5-K)") (class "Default")
      (node (ref "DB5") (pin "2") (pinfunction "K_2") (pintype "passive"))
      (node (ref "RB5") (pin "2") (pinfunction "2_2") (pintype "passive"))
    )
    (net (code "106") (name "Net-(DB6-K)") (class "Default")
      (node (ref "DB6") (pin "2") (pinfunction "K_2") (pintype "passive"))
      (node (ref "RB6") (pin "2") (pinfunction "2_2") (pintype "passive"))
    )
    (net (code "107") (name "Net-(DB7-K)") (class "Default")
      (node (ref "DB7") (pin "2") (pinfunction "K_2") (pintype "passive"))
      (node (ref "RB7") (pin "2") (pinfunction "2_2") (pintype "passive"))
    )
    (net (code "108") (name "Net-(DB8-K)") (class "Default")
      (node (ref "DB8") (pin "2") (pinfunction "K_2") (pintype "passive"))
      (node (ref "RB8") (pin "2") (pinfunction "2_2") (pintype "passive"))
    )
    (net (code "109") (name "Net-(DB9-K)") (class "Default")
      (node (ref "DB9") (pin "2") (pinfunction "K_2") (pintype "passive"))
      (node (ref "RB9") (pin "2") (pinfunction "2_2") (pintype "passive"))
    )
    (net (code "110") (name "Net-(DB10-K)") (class "Default")
      (node (ref "DB10") (pin "2") (pinfunction "K_2") (pintype "passive"))
      (node (ref "RB10") (pin "2") (pinfunction "2_2") (pintype "passive"))
    )
    (net (code "111") (name "Net-(DB11-K)") (class "Default")
      (node (ref "DB11") (pin "2") (pinfunction "K_2") (pintype "passive"))
      (node (ref "RB11") (pin "2") (pinfunction "2_2") (pintype "passive"))
    )
    (net (code "112") (name "Net-(DB12-K)") (class "Default")
      (node (ref "DB12") (pin "2") (pinfunction "K_2") (pintype "passive"))
      (node (ref "RB12") (pin "2") (pinfunction "2_2") (pintype "passive"))
    )
    (net (code "113") (name "Net-(DB13-K)") (class "Default")
      (node (ref "DB13") (pin "2") (pinfunction "K_2") (pintype "passive"))
      (node (ref "RB13") (pin "2") (pinfunction "2_2") (pintype "passive"))
    )
    (net (code "114") (name "Net-(DB14-K)") (class "Default")
      (node (ref "DB14") (pin "2") (pinfunction "K_2") (pintype "passive"))
      (node (ref "RB14") (pin "2") (pinfunction "2_2") (pintype "passive"))
    )
    (net (code "115") (name "Net-(DB15-K)") (class "Default")
      (node (ref "DB15") (pin "2") (pinfunction "K_2") (pintype "passive"))
      (node (ref "RB15") (pin "2") (pinfunction "2_2") (pintype "passive"))
    )
    (net (code "116") (name "Net-(DG0-K)") (class "Default")
      (node (ref "DG0") (pin "2") (pinfunction "K_2") (pintype "passive"))
      (node (ref "RG0") (pin "2") (pinfunction "2_2") (pintype "passive"))
    )
    (net (code "117") (name "Net-(DG1-K)") (class "Default")
      (node (ref "DG1") (pin "2") (pinfunction "K_2") (pintype "passive"))
      (node (ref "RG1") (pin "2") (pinfunction "2_2") (pintype "passive"))
    )
    (net (code "118") (name "Net-(DG2-K)") (class "Default")
      (node (ref "DG2") (pin "2") (pinfunction "K_2") (pintype "passive"))
      (node (ref "RG2") (pin "2") (pinfunction "2_2") (pintype "passive"))
    )
    (net (code "119") (name "Net-(DG3-K)") (class "Default")
      (node (ref "DG3") (pin "2") (pinfunction "K_2") (pintype "passive"))
      (node (ref "RG3") (pin "2") (pinfunction "2_2") (pintype "passive"))
    )
    (net (code "120") (name "Net-(DG4-K)") (class "Default")
      (node (ref "DG4") (pin "2") (pinfunction "K_2") (pintype "passive"))
      (node (ref "RG4") (pin "2") (pinfunction "2_2") (pintype "passive"))
    )
    (net (code "121") (name "Net-(DG5-K)") (class "Default")
      (node (ref "DG5") (pin "2") (pinfunction "K_2") (pintype "passive"))
      (node (ref "RG5") (pin "2") (pinfunction "2_2") (pintype "passive"))
    )
    (net (code "122") (name "Net-(DG6-K)") (class "Default")
      (node (ref "DG6") (pin "2") (pinfunction "K_2") (pintype "passive"))
      (node (ref "RG6") (pin "2") (pinfunction "2_2") (pintype "passive"))
    )
    (net (code "123") (name "Net-(DG7-K)") (class "Default")
      (node (ref "DG7") (pin "2") (pinfunction "K_2") (pintype "passive"))
      (node (ref "RG7") (pin "2") (pinfunction "2_2") (pintype "passive"))
    )
    (net (code "124") (name "Net-(DG8-K)") (class "Default")
      (node (ref "DG8") (pin "2") (pinfunction "K_2") (pintype "passive"))
      (node (ref "RG8") (pin "2") (pinfunction "2_2") (pintype "passive"))
    )
    (net (code "125") (name "Net-(DG9-K)") (class "Default")
      (node (ref "DG9") (pin "2") (pinfunction "K_2") (pintype "passive"))
      (node (ref "RG9") (pin "2") (pinfunction "2_2") (pintype "passive"))
    )
    (net (code "126") (name "Net-(DG10-K)") (class "Default")
      (node (ref "DG10") (pin "2") (pinfunction "K_2") (pintype "passive"))
      (node (ref "RG10") (pin "2") (pinfunction "2_2") (pintype "passive"))
    )
    (net (code "127") (name "Net-(DG11-K)") (class "Default")
      (node (ref "DG11") (pin "2") (pinfunction "K_2") (pintype "passive"))
      (node (ref "RG11") (pin "2") (pinfunction "2_2") (pintype "passive"))
    )
    (net (code "128") (name "Net-(DG12-K)") (class "Default")
      (node (ref "DG12") (pin "2") (pinfunction "K_2") (pintype "passive"))
      (node (ref "RG12") (pin "2") (pinfunction "2_2") (pintype "passive"))
    )
    (net (code "129") (name "Net-(DG13-K)") (class "Default")
      (node (ref "DG13") (pin "2") (pinfunction "K_2") (pintype "passive"))
      (node (ref "RG13") (pin "2") (pinfunction "2_2") (pintype "passive"))
    )
    (net (code "130") (name "Net-(DG14-K)") (class "Default")
      (node (ref "DG14") (pin "2") (pinfunction "K_2") (pintype "passive"))
      (node (ref "RG14") (pin "2") (pinfunction "2_2") (pintype "passive"))
    )
    (net (code "131") (name "Net-(DG15-K)") (class "Default")
      (node (ref "DG15") (pin "2") (pinfunction "K_2") (pintype "passive"))
      (node (ref "RG15") (pin "2") (pinfunction "2_2") (pintype "passive"))
    )
    (net (code "132") (name "Net-(DR0-K)") (class "Default")
      (node (ref "DR0") (pin "2") (pinfunction "K_2") (pintype "passive"))
      (node (ref "RR0") (pin "2") (pinfunction "2_2") (pintype "passive"))
    )
    (net (code "133") (name "Net-(DR1-K)") (class "Default")
      (node (ref "DR1") (pin "2") (pinfunction "K_2") (pintype "passive"))
      (node (ref "RR1") (pin "2") (pinfunction "2_2") (pintype "passive"))
    )
    (net (code "134") (name "Net-(DR2-K)") (class "Default")
      (node (ref "DR2") (pin "2") (pinfunction "K_2") (pintype "passive"))
      (node (ref "RR2") (pin "2") (pinfunction "2_2") (pintype "passive"))
    )
    (net (code "135") (name "Net-(DR3-K)") (class "Default")
      (node (ref "DR3") (pin "2") (pinfunction "K_2") (pintype "passive"))
      (node (ref "RR3") (pin "2") (pinfunction "2_2") (pintype "passive"))
    )
    (net (code "136") (name "Net-(DR4-K)") (class "Default")
      (node (ref "DR4") (pin "2") (pinfunction "K_2") (pintype "passive"))
      (node (ref "RR4") (pin "2") (pinfunction "2_2") (pintype "passive"))
    )
    (net (code "137") (name "Net-(DR5-K)") (class "Default")
      (node (ref "DR5") (pin "2") (pinfunction "K_2") (pintype "passive"))
      (node (ref "RR5") (pin "2") (pinfunction "2_2") (pintype "passive"))
    )
    (net (code "138") (name "Net-(DR6-K)") (class "Default")
      (node (ref "DR6") (pin "2") (pinfunction "K_2") (pintype "passive"))
      (node (ref "RR6") (pin "2") (pinfunction "2_2") (pintype "passive"))
    )
    (net (code "139") (name "Net-(DR7-K)") (class "Default")
      (node (ref "DR7") (pin "2") (pinfunction "K_2") (pintype "passive"))
      (node (ref "RR7") (pin "2") (pinfunction "2_2") (pintype "passive"))
    )
    (net (code "140") (name "Net-(DR8-K)") (class "Default")
      (node (ref "DR8") (pin "2") (pinfunction "K_2") (pintype "passive"))
      (node (ref "RR8") (pin "2") (pinfunction "2_2") (pintype "passive"))
    )
    (net (code "141") (name "Net-(DR9-K)") (class "Default")
      (node (ref "DR9") (pin "2") (pinfunction "K_2") (pintype "passive"))
      (node (ref "RR9") (pin "2") (pinfunction "2_2") (pintype "passive"))
    )
    (net (code "142") (name "Net-(DR10-K)") (class "Default")
      (node (ref "DR10") (pin "2") (pinfunction "K_2") (pintype "passive"))
      (node (ref "RR10") (pin "2") (pinfunction "2_2") (pintype "passive"))
    )
    (net (code "143") (name "Net-(DR11-K)") (class "Default")
      (node (ref "DR11") (pin "2") (pinfunction "K_2") (pintype "passive"))
      (node (ref "RR11") (pin "2") (pinfunction "2_2") (pintype "passive"))
    )
    (net (code "144") (name "Net-(DR12-K)") (class "Default")
      (node (ref "DR12") (pin "2") (pinfunction "K_2") (pintype "passive"))
      (node (ref "RR12") (pin "2") (pinfunction "2_2") (pintype "passive"))
    )
    (net (code "145") (name "Net-(DR13-K)") (class "Default")
      (node (ref "DR13") (pin "2") (pinfunction "K_2") (pintype "passive"))
      (node (ref "RR13") (pin "2") (pinfunction "2_2") (pintype "passive"))
    )
    (net (code "146") (name "Net-(DR14-K)") (class "Default")
      (node (ref "DR14") (pin "2") (pinfunction "K_2") (pintype "passive"))
      (node (ref "RR14") (pin "2") (pinfunction "2_2") (pintype "passive"))
    )
    (net (code "147") (name "Net-(DR15-K)") (class "Default")
      (node (ref "DR15") (pin "2") (pinfunction "K_2") (pintype "passive"))
      (node (ref "RR15") (pin "2") (pinfunction "2_2") (pintype "passive"))
    )
    (net (code "148") (name "Net-(LedRun-A)") (class "Default")
      (node (ref "LedRun") (pin "1") (pinfunction "A_1") (pintype "passive"))
      (node (ref "RledRun") (pin "1") (pinfunction "1_1") (pintype "passive"))
    )
    (net (code "149") (name "Net-(LedSyncG-A)") (class "Default")
      (node (ref "LedSyncG") (pin "1") (pinfunction "A_1") (pintype "passive"))
      (node (ref "RledSynchroR") (pin "1") (pinfunction "1_1") (pintype "passive"))
    )
    (net (code "150") (name "Net-(LedSyncR-A)") (class "Default")
      (node (ref "LedSyncR") (pin "1") (pinfunction "A_1") (pintype "passive"))
      (node (ref "RledSynchroG") (pin "1") (pinfunction "1_1") (pintype "passive"))
    )
    (net (code "151") (name "Net-(LedUsr-A)") (class "Default")
      (node (ref "LedUsr") (pin "1") (pinfunction "A_1") (pintype "passive"))
      (node (ref "RledUsr") (pin "1") (pinfunction "1_1") (pintype "passive"))
    )
    (net (code "152") (name "Net-(MICRO_SD-CS)") (class "Default")
      (node (ref "MICRO_SD") (pin "2") (pinfunction "CS_2") (pintype "passive"))
      (node (ref "RsdCS") (pin "2") (pinfunction "2_2") (pintype "passive"))
    )
    (net (code "153") (name "Net-(MICRO_SD-DI)") (class "Default")
      (node (ref "MICRO_SD") (pin "3") (pinfunction "DI_3") (pintype "passive"))
      (node (ref "RsdMosi") (pin "2") (pinfunction "2_2") (pintype "passive"))
    )
    (net (code "154") (name "Net-(MICRO_SD-DO)") (class "Default")
      (node (ref "MICRO_SD") (pin "7") (pinfunction "DO_7") (pintype "passive"))
      (node (ref "RsdMiso") (pin "2") (pinfunction "2_2") (pintype "passive"))
    )
    (net (code "155") (name "Net-(MICRO_SD-SCLK)") (class "Default")
      (node (ref "MICRO_SD") (pin "5") (pinfunction "SCLK_5") (pintype "passive"))
      (node (ref "RsdSck") (pin "2") (pinfunction "2_2") (pintype "passive"))
    )
    (net (code "156") (name "Net-(QRF-D)") (class "Default")
      (node (ref "QRF") (pin "3") (pinfunction "D_3") (pintype "passive"))
      (node (ref "RC1240") (pin "22") (pinfunction "RESET_22") (pintype "passive"))
    )
    (net (code "157") (name "Net-(QXbee-D)") (class "Default")
      (node (ref "QXbee") (pin "3") (pinfunction "D_3") (pintype "passive"))
      (node (ref "Uxbee") (pin "5") (pinfunction "RESET_5") (pintype "output"))
    )
    (net (code "158") (name "Net-(RpuU1tx-Pad1)") (class "Default")
      (node (ref "RpuU1tx") (pin "1") (pinfunction "1_1") (pintype "passive"))
      (node (ref "RsU1tx") (pin "1") (pinfunction "1_1") (pintype "passive"))
      (node (ref "UART") (pin "2") (pinfunction "2_2") (pintype "passive"))
    )
    (net (code "159") (name "Net-(Rsu1rx-Pad2)") (class "Default")
      (node (ref "Rsu1rx") (pin "2") (pinfunction "2_2") (pintype "passive"))
      (node (ref "UART") (pin "3") (pinfunction "3_3") (pintype "passive"))
    )
    (net (code "160") (name "Net-(STM32A-PH0-OSC_IN(PH0))") (class "Default")
      (node (ref "C46") (pin "2") (pinfunction "2_2") (pintype "passive"))
      (node (ref "STM32") (pin "12") (pinfunction "PH0-OSC_IN(PH0)_12") (pintype "bidirectional"))
      (node (ref "Y1") (pin "2") (pinfunction "OSC2_2") (pintype "passive"))
    )
    (net (code "161") (name "Net-(STM32A-PH1-OSC_OUT(PH1))") (class "Default")
      (node (ref "C47") (pin "2") (pinfunction "2_2") (pintype "passive"))
      (node (ref "STM32") (pin "13") (pinfunction "PH1-OSC_OUT(PH1)_13") (pintype "bidirectional"))
      (node (ref "Y1") (pin "1") (pinfunction "OSC1_1") (pintype "passive"))
    )
    (net (code "162") (name "Net-(STM32A-VCAP_1)") (class "Default")
      (node (ref "C49") (pin "2") (pinfunction "2_2") (pintype "passive"))
      (node (ref "STM32") (pin "49") (pinfunction "VCAP_1_49") (pintype "power_in"))
    )
    (net (code "163") (name "Net-(STM32A-VCAP_2)") (class "Default")
      (node (ref "C50") (pin "2") (pinfunction "2_2") (pintype "passive"))
      (node (ref "STM32") (pin "73") (pinfunction "VCAP_2_73") (pintype "power_in"))
    )
    (net (code "164") (name "Net-(USB-D+)") (class "Default")
      (node (ref "USB") (pin "3") (pinfunction "D+_3") (pintype "passive"))
      (node (ref "USB_ESD") (pin "5") (pinfunction "D+Out_5") (pintype "bidirectional"))
    )
    (net (code "165") (name "Net-(USB-D-)") (class "Default")
      (node (ref "USB") (pin "2") (pinfunction "D-_2") (pintype "passive"))
      (node (ref "USB_ESD") (pin "4") (pinfunction "D-Out_4") (pintype "bidirectional"))
    )
    (net (code "166") (name "VDD_RC1240") (class "Default")
      (node (ref "RC1240") (pin "11") (pinfunction "VDD_11") (pintype "passive"))
      (node (ref "RC1240") (pin "2") (pinfunction "CTS/RXTX/RXEN_2") (pintype "passive"))
      (node (ref "RC1240") (pin "3") (pinfunction "RTX/TXEN_3") (pintype "passive"))
    )
    (net (code "167") (name "unconnected-(Antenne_433-Pad2)") (class "Default")
      (node (ref "Antenne_433") (pin "2") (pinfunction "2_2") (pintype "passive+no_connect"))
    )
    (net (code "168") (name "unconnected-(HE10-Pad7)") (class "Default")
      (node (ref "HE10") (pin "7") (pinfunction "7_7") (pintype "passive"))
    )
    (net (code "169") (name "unconnected-(HE10-Pad14)") (class "Default")
      (node (ref "HE10") (pin "14") (pinfunction "14_14") (pintype "passive"))
    )
    (net (code "170") (name "unconnected-(MICRO_SD-Nail-Pad10)") (class "Default")
      (node (ref "MICRO_SD") (pin "10") (pinfunction "Nail_10") (pintype "passive"))
    )
    (net (code "171") (name "unconnected-(MICRO_SD-X-Pad1)") (class "Default")
      (node (ref "MICRO_SD") (pin "1") (pinfunction "X_1") (pintype "passive+no_connect"))
    )
    (net (code "172") (name "unconnected-(MICRO_SD-X-Pad8)") (class "Default")
      (node (ref "MICRO_SD") (pin "8") (pinfunction "X_8") (pintype "passive+no_connect"))
    )
    (net (code "173") (name "unconnected-(RC1240---Pad15)") (class "Default")
      (node (ref "RC1240") (pin "15") (pinfunction "-_15") (pintype "passive+no_connect"))
    )
    (net (code "174") (name "unconnected-(RC1240---Pad16)") (class "Default")
      (node (ref "RC1240") (pin "16") (pinfunction "-_16") (pintype "passive+no_connect"))
    )
    (net (code "175") (name "unconnected-(RC1240---Pad17)") (class "Default")
      (node (ref "RC1240") (pin "17") (pinfunction "-_17") (pintype "passive+no_connect"))
    )
    (net (code "176") (name "unconnected-(RC1240---Pad18)") (class "Default")
      (node (ref "RC1240") (pin "18") (pinfunction "-_18") (pintype "passive+no_connect"))
    )
    (net (code "177") (name "unconnected-(RC1240---Pad19)") (class "Default")
      (node (ref "RC1240") (pin "19") (pinfunction "-_19") (pintype "passive+no_connect"))
    )
    (net (code "178") (name "unconnected-(RC1240---Pad20)") (class "Default")
      (node (ref "RC1240") (pin "20") (pinfunction "-_20") (pintype "passive+no_connect"))
    )
    (net (code "179") (name "unconnected-(RC1240---Pad21)") (class "Default")
      (node (ref "RC1240") (pin "21") (pinfunction "-_21") (pintype "passive+no_connect"))
    )
    (net (code "180") (name "unconnected-(RC1240---Pad25)") (class "Default")
      (node (ref "RC1240") (pin "25") (pinfunction "-_25") (pintype "passive+no_connect"))
    )
    (net (code "181") (name "unconnected-(RC1240---Pad26)") (class "Default")
      (node (ref "RC1240") (pin "26") (pinfunction "-_26") (pintype "passive+no_connect"))
    )
    (net (code "182") (name "unconnected-(RC1240---Pad27)") (class "Default")
      (node (ref "RC1240") (pin "27") (pinfunction "-_27") (pintype "passive+no_connect"))
    )
    (net (code "183") (name "unconnected-(RC1240---Pad28)") (class "Default")
      (node (ref "RC1240") (pin "28") (pinfunction "-_28") (pintype "passive+no_connect"))
    )
    (net (code "184") (name "unconnected-(RC1240---Pad29)") (class "Default")
      (node (ref "RC1240") (pin "29") (pinfunction "-_29") (pintype "passive+no_connect"))
    )
    (net (code "185") (name "unconnected-(RC1240---Pad30)") (class "Default")
      (node (ref "RC1240") (pin "30") (pinfunction "-_30") (pintype "passive+no_connect"))
    )
    (net (code "186") (name "unconnected-(RC1240-LNA_EN-Pad24)") (class "Default")
      (node (ref "RC1240") (pin "24") (pinfunction "LNA_EN_24") (pintype "passive+no_connect"))
    )
    (net (code "187") (name "unconnected-(RC1240-PA_EN-Pad23)") (class "Default")
      (node (ref "RC1240") (pin "23") (pinfunction "PA_EN_23") (pintype "passive+no_connect"))
    )
    (net (code "188") (name "unconnected-(STM32A-PA7-Pad32)") (class "Default")
      (node (ref "STM32") (pin "32") (pinfunction "PA7_32") (pintype "bidirectional"))
    )
    (net (code "189") (name "unconnected-(STM32A-PA15(JTDI)-Pad77)") (class "Default")
      (node (ref "STM32") (pin "77") (pinfunction "PA15(JTDI)_77") (pintype "bidirectional"))
    )
    (net (code "190") (name "unconnected-(STM32A-PB0-Pad35)") (class "Default")
      (node (ref "STM32") (pin "35") (pinfunction "PB0_35") (pintype "bidirectional"))
    )
    (net (code "191") (name "unconnected-(STM32A-PB1-Pad36)") (class "Default")
      (node (ref "STM32") (pin "36") (pinfunction "PB1_36") (pintype "bidirectional"))
    )
    (net (code "192") (name "unconnected-(STM32A-PB2-BOOT1(PB2)-Pad37)") (class "Default")
      (node (ref "STM32") (pin "37") (pinfunction "PB2-BOOT1(PB2)_37") (pintype "bidirectional"))
    )
    (net (code "193") (name "unconnected-(STM32A-PB4(NJTRST)-Pad90)") (class "Default")
      (node (ref "STM32") (pin "90") (pinfunction "PB4(NJTRST)_90") (pintype "bidirectional"))
    )
    (net (code "194") (name "unconnected-(STM32A-PB5-Pad91)") (class "Default")
      (node (ref "STM32") (pin "91") (pinfunction "PB5_91") (pintype "bidirectional"))
    )
    (net (code "195") (name "unconnected-(STM32A-PB9-Pad96)") (class "Default")
      (node (ref "STM32") (pin "96") (pinfunction "PB9_96") (pintype "bidirectional"))
    )
    (net (code "196") (name "unconnected-(STM32A-PD5-Pad86)") (class "Default")
      (node (ref "STM32") (pin "86") (pinfunction "PD5_86") (pintype "bidirectional"))
    )
    (net (code "197") (name "unconnected-(STM32A-PD6-Pad87)") (class "Default")
      (node (ref "STM32") (pin "87") (pinfunction "PD6_87") (pintype "bidirectional"))
    )
    (net (code "198") (name "unconnected-(STM32A-PD7-Pad88)") (class "Default")
      (node (ref "STM32") (pin "88") (pinfunction "PD7_88") (pintype "bidirectional"))
    )
    (net (code "199") (name "unconnected-(STM32A-PD8-Pad55)") (class "Default")
      (node (ref "STM32") (pin "55") (pinfunction "PD8_55") (pintype "bidirectional"))
    )
    (net (code "200") (name "unconnected-(STM32A-PD9-Pad56)") (class "Default")
      (node (ref "STM32") (pin "56") (pinfunction "PD9_56") (pintype "bidirectional"))
    )
    (net (code "201") (name "unconnected-(STM32A-PD11-Pad58)") (class "Default")
      (node (ref "STM32") (pin "58") (pinfunction "PD11_58") (pintype "bidirectional"))
    )
    (net (code "202") (name "unconnected-(STM32A-PD12-Pad59)") (class "Default")
      (node (ref "STM32") (pin "59") (pinfunction "PD12_59") (pintype "bidirectional"))
    )
    (net (code "203") (name "unconnected-(STM32A-PD13-Pad60)") (class "Default")
      (node (ref "STM32") (pin "60") (pinfunction "PD13_60") (pintype "bidirectional"))
    )
    (net (code "204") (name "unconnected-(STM32A-PD14-Pad61)") (class "Default")
      (node (ref "STM32") (pin "61") (pinfunction "PD14_61") (pintype "bidirectional"))
    )
    (net (code "205") (name "unconnected-(Ucan-VREF-Pad5)") (class "Default")
      (node (ref "Ucan") (pin "5") (pinfunction "VREF_5") (pintype "output"))
    )
    (net (code "206") (name "unconnected-(Uxbee-CTS-Pad12)") (class "Default")
      (node (ref "Uxbee") (pin "12") (pinfunction "CTS_12") (pintype "output"))
    )
    (net (code "207") (name "unconnected-(Uxbee-DI0-Pad20)") (class "Default")
      (node (ref "Uxbee") (pin "20") (pinfunction "DI0_20") (pintype "passive"))
    )
    (net (code "208") (name "unconnected-(Uxbee-DI1-Pad19)") (class "Default")
      (node (ref "Uxbee") (pin "19") (pinfunction "DI1_19") (pintype "passive"))
    )
    (net (code "209") (name "unconnected-(Uxbee-DI2-Pad18)") (class "Default")
      (node (ref "Uxbee") (pin "18") (pinfunction "DI2_18") (pintype "passive"))
    )
    (net (code "210") (name "unconnected-(Uxbee-DI3-Pad17)") (class "Default")
      (node (ref "Uxbee") (pin "17") (pinfunction "DI3_17") (pintype "passive"))
    )
    (net (code "211") (name "unconnected-(Uxbee-DI4-Pad11)") (class "Default")
      (node (ref "Uxbee") (pin "11") (pinfunction "DI4_11") (pintype "passive"))
    )
    (net (code "212") (name "unconnected-(Uxbee-DI5-Pad15)") (class "Default")
      (node (ref "Uxbee") (pin "15") (pinfunction "DI5_15") (pintype "passive"))
    )
    (net (code "213") (name "unconnected-(Uxbee-DI8-Pad9)") (class "Default")
      (node (ref "Uxbee") (pin "9") (pinfunction "DI8_9") (pintype "passive"))
    )
    (net (code "214") (name "unconnected-(Uxbee-DO8-Pad4)") (class "Default")
      (node (ref "Uxbee") (pin "4") (pinfunction "DO8_4") (pintype "passive"))
    )
    (net (code "215") (name "unconnected-(Uxbee-NC-Pad8)") (class "Default")
      (node (ref "Uxbee") (pin "8") (pinfunction "NC_8") (pintype "output"))
    )
    (net (code "216") (name "unconnected-(Uxbee-ON-Pad13)") (class "Default")
      (node (ref "Uxbee") (pin "13") (pinfunction "ON_13") (pintype "output"))
    )
    (net (code "217") (name "unconnected-(Uxbee-PWM0-Pad6)") (class "Default")
      (node (ref "Uxbee") (pin "6") (pinfunction "PWM0_6") (pintype "passive"))
    )
    (net (code "218") (name "unconnected-(Uxbee-PWM1-Pad7)") (class "Default")
      (node (ref "Uxbee") (pin "7") (pinfunction "PWM1_7") (pintype "passive"))
    )
    (net (code "219") (name "unconnected-(Uxbee-RTS-Pad16)") (class "Default")
      (node (ref "Uxbee") (pin "16") (pinfunction "RTS_16") (pintype "output"))
    )
    (net (code "220") (name "unconnected-(Uxbee-VREF-Pad14)") (class "Default")
      (node (ref "Uxbee") (pin "14") (pinfunction "VREF_14") (pintype "output"))
    )
  )
)
